# Main_Power.net
KiCad netlist of a schematic drawn in Altium Designer
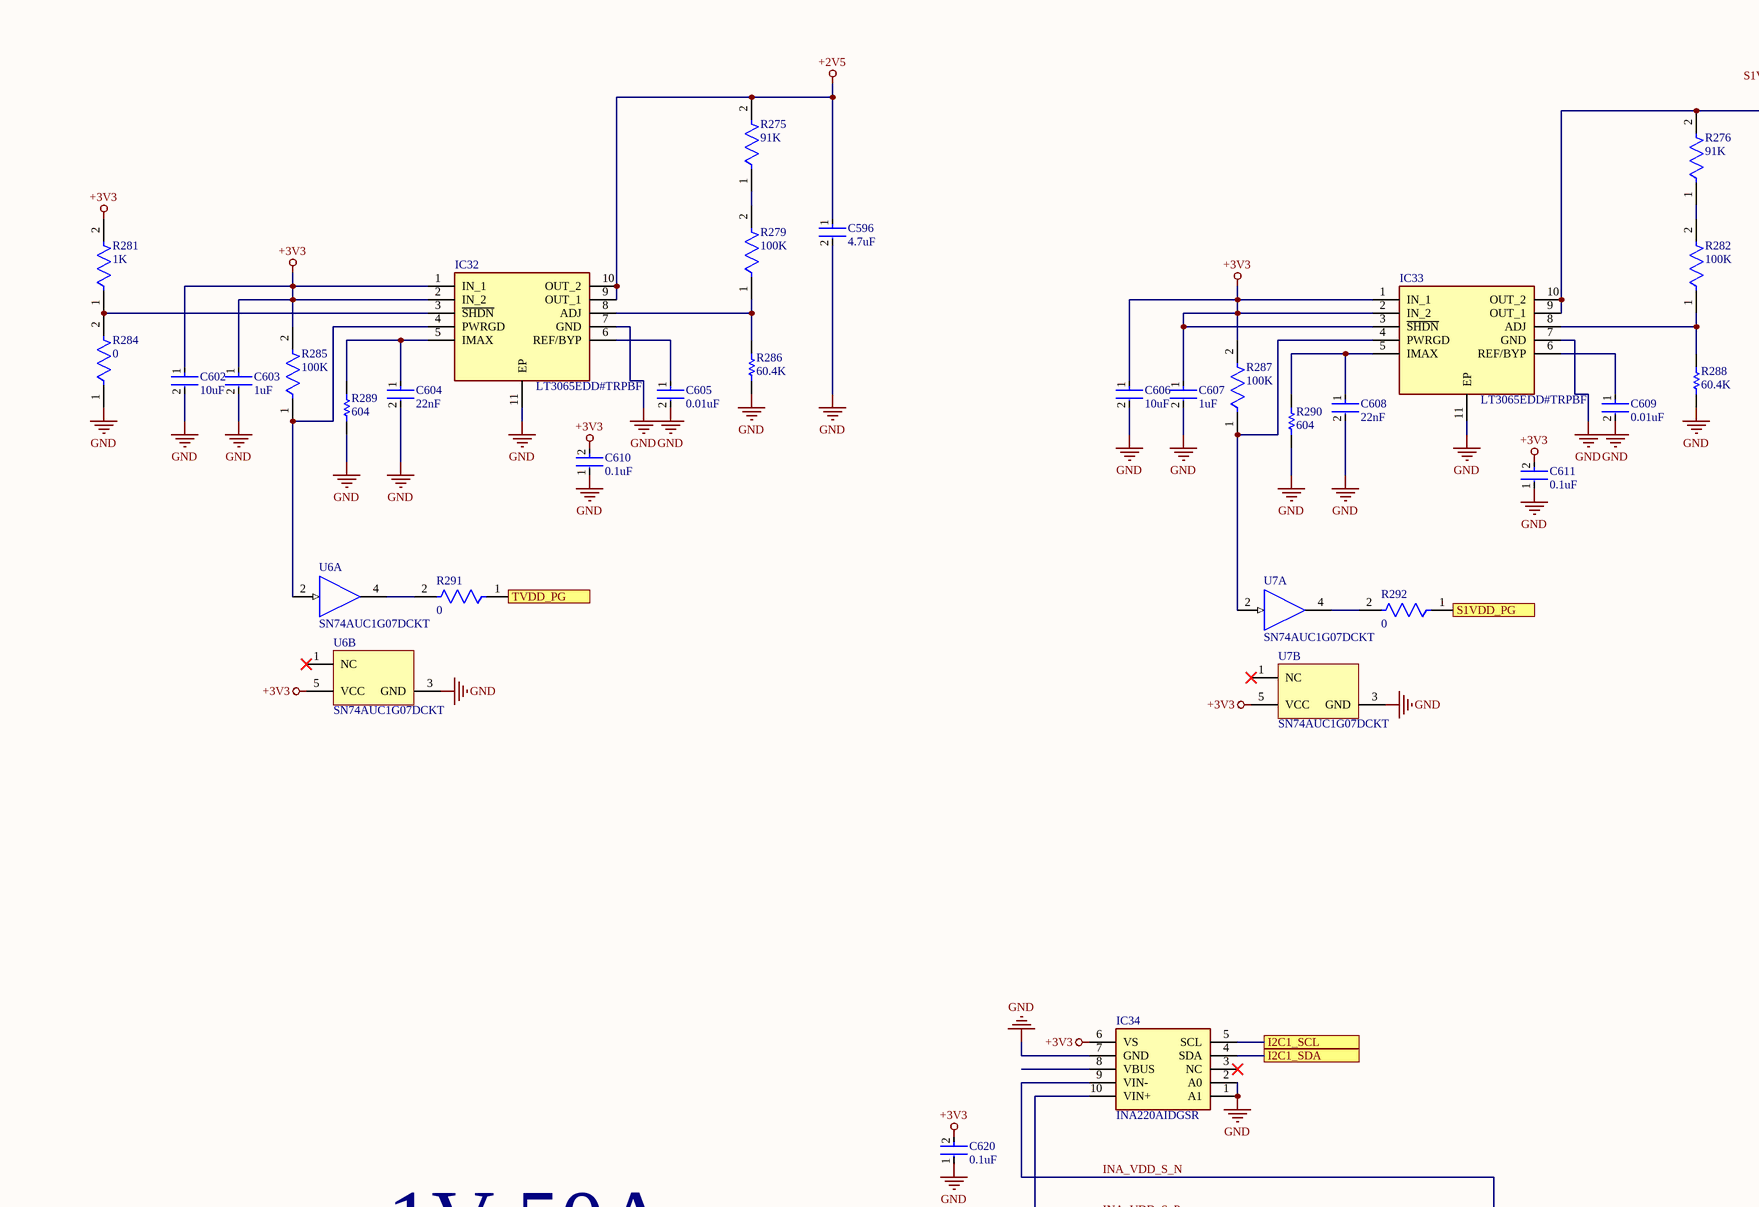
[diagram p0: Main_Power.SchDoc, top left]
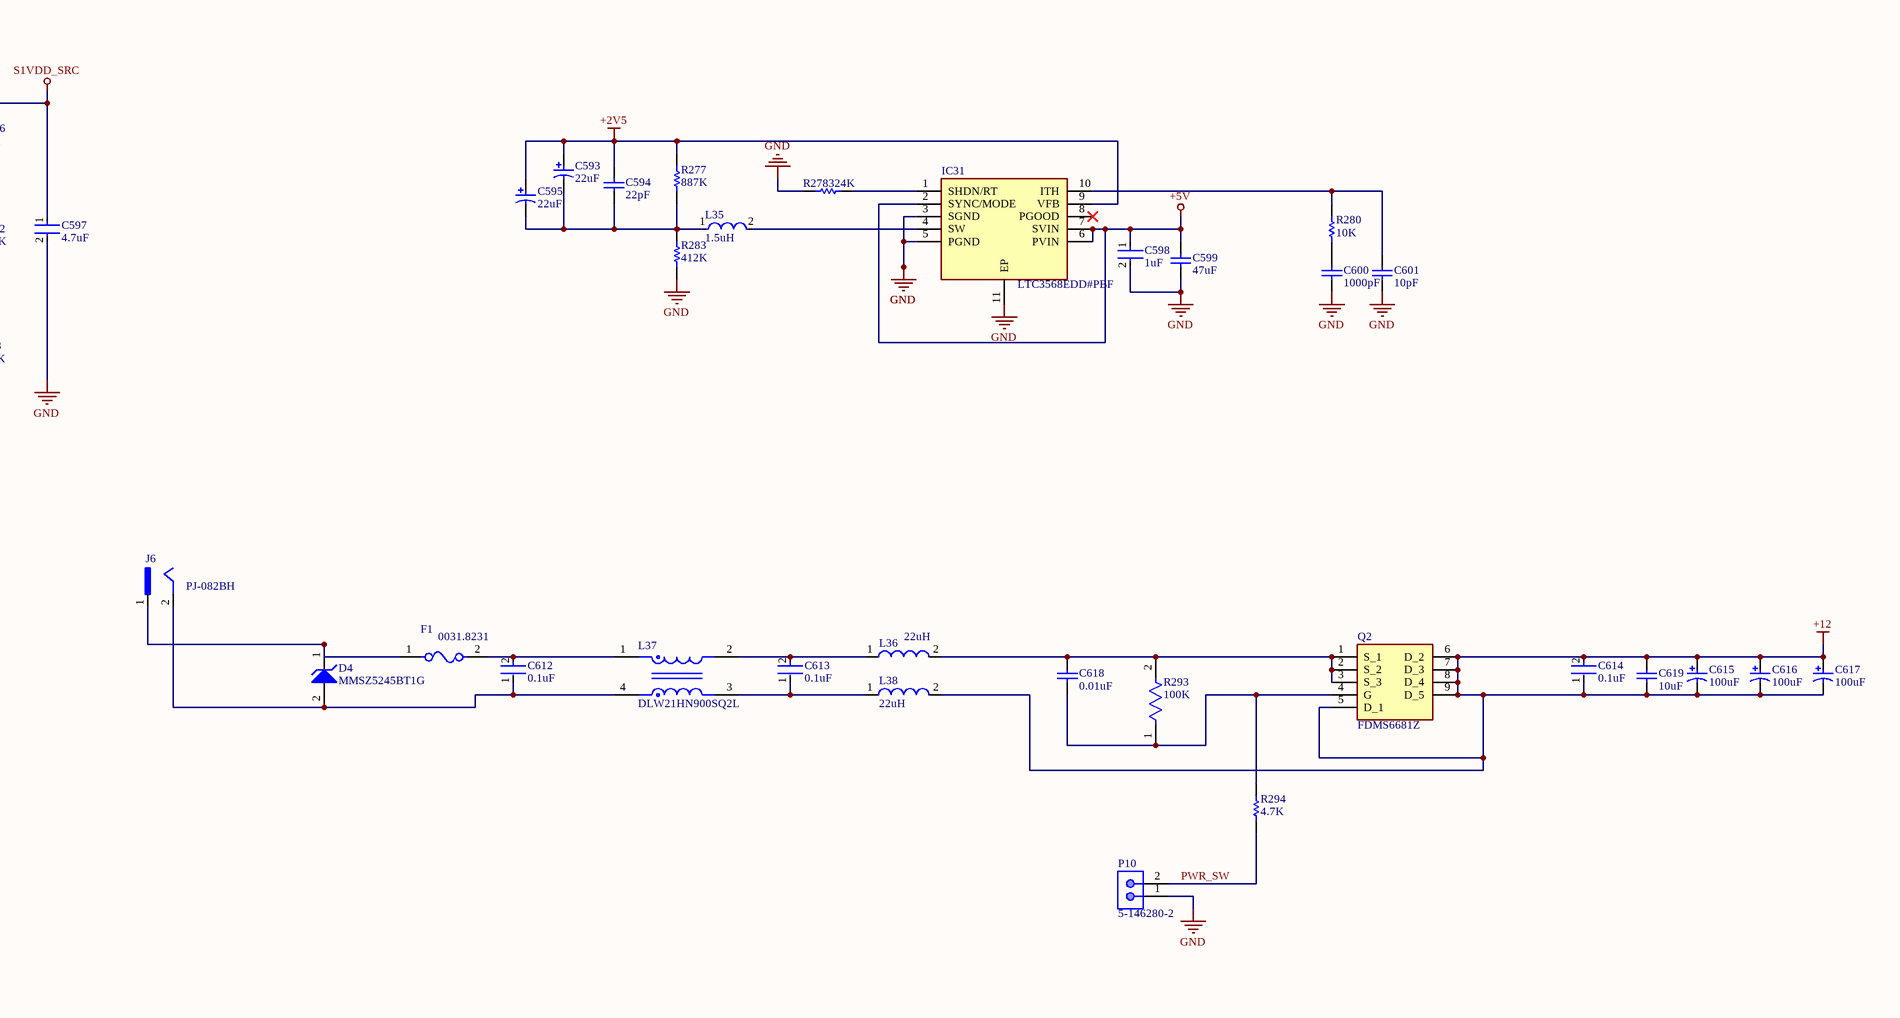
[diagram p1: Main_Power.SchDoc, top right]
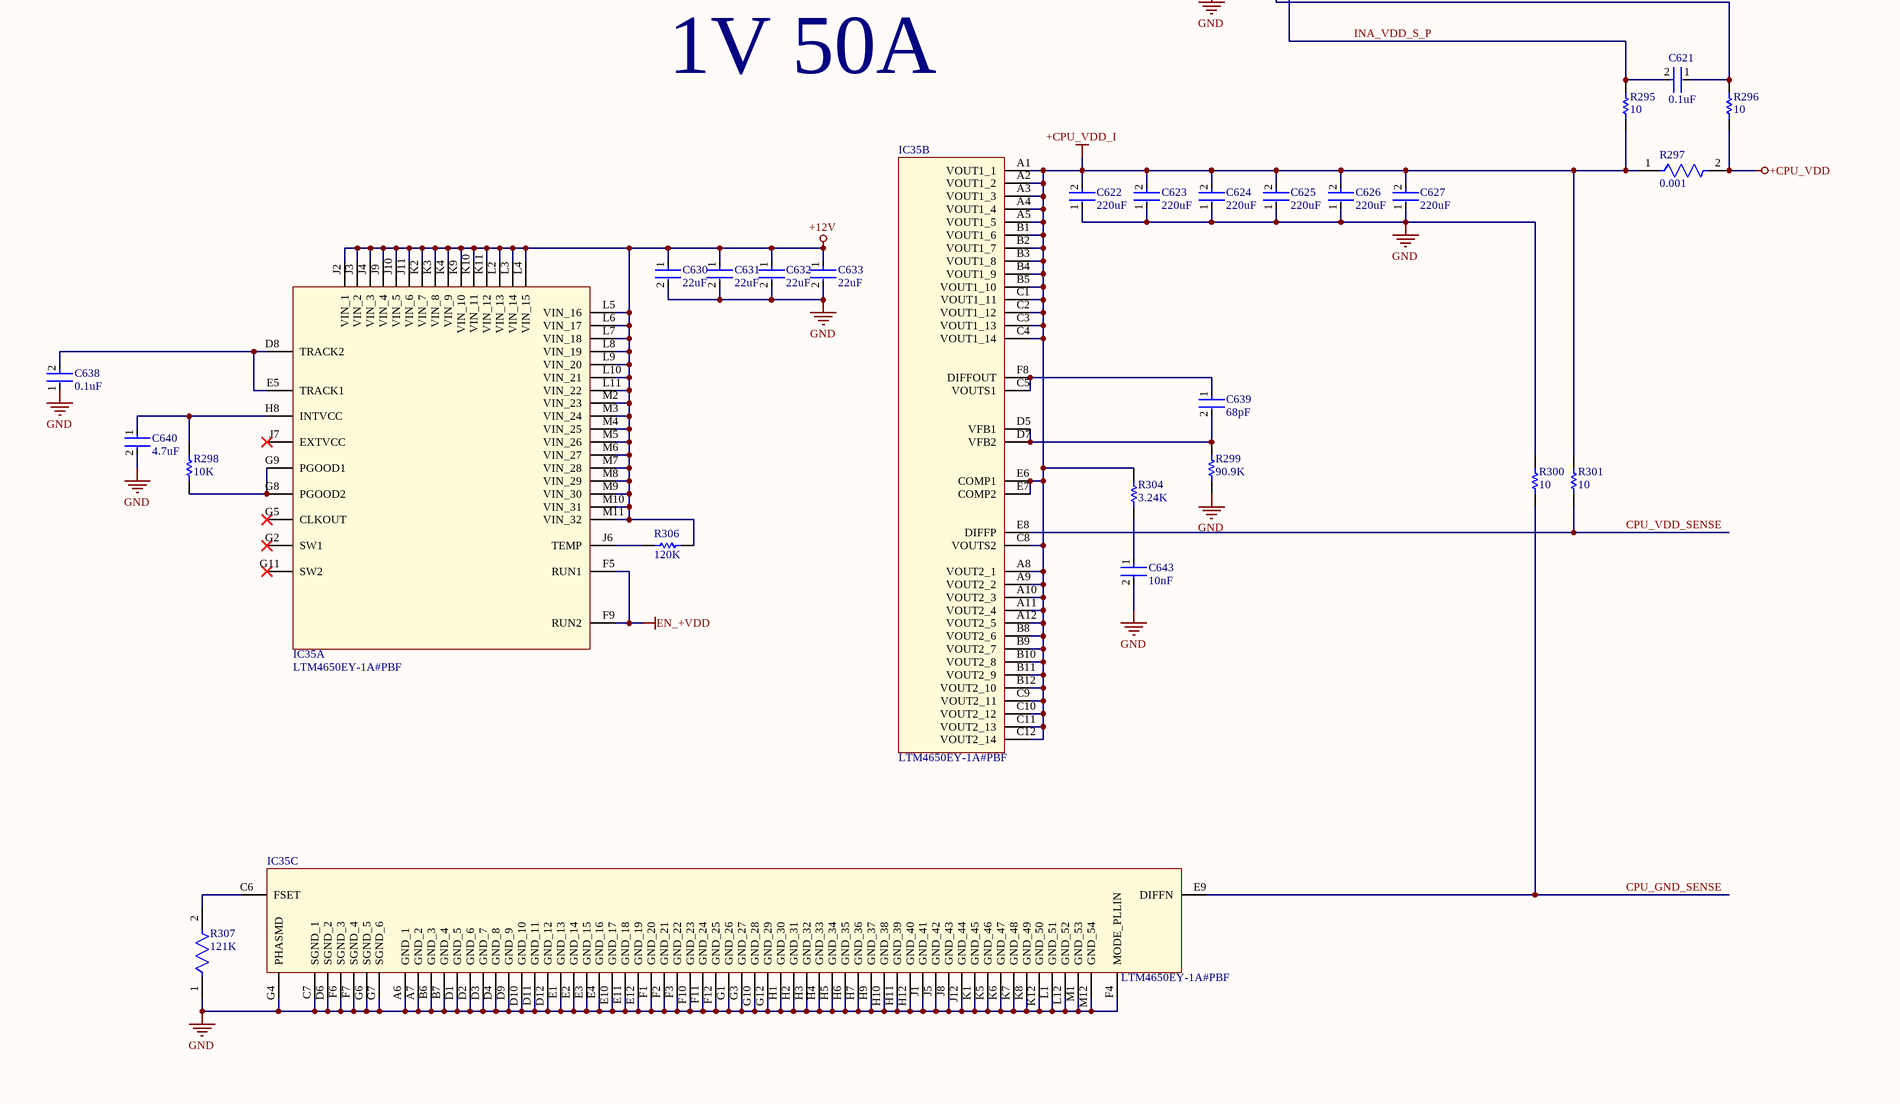
[diagram p2: Main_Power.SchDoc, bottom left]
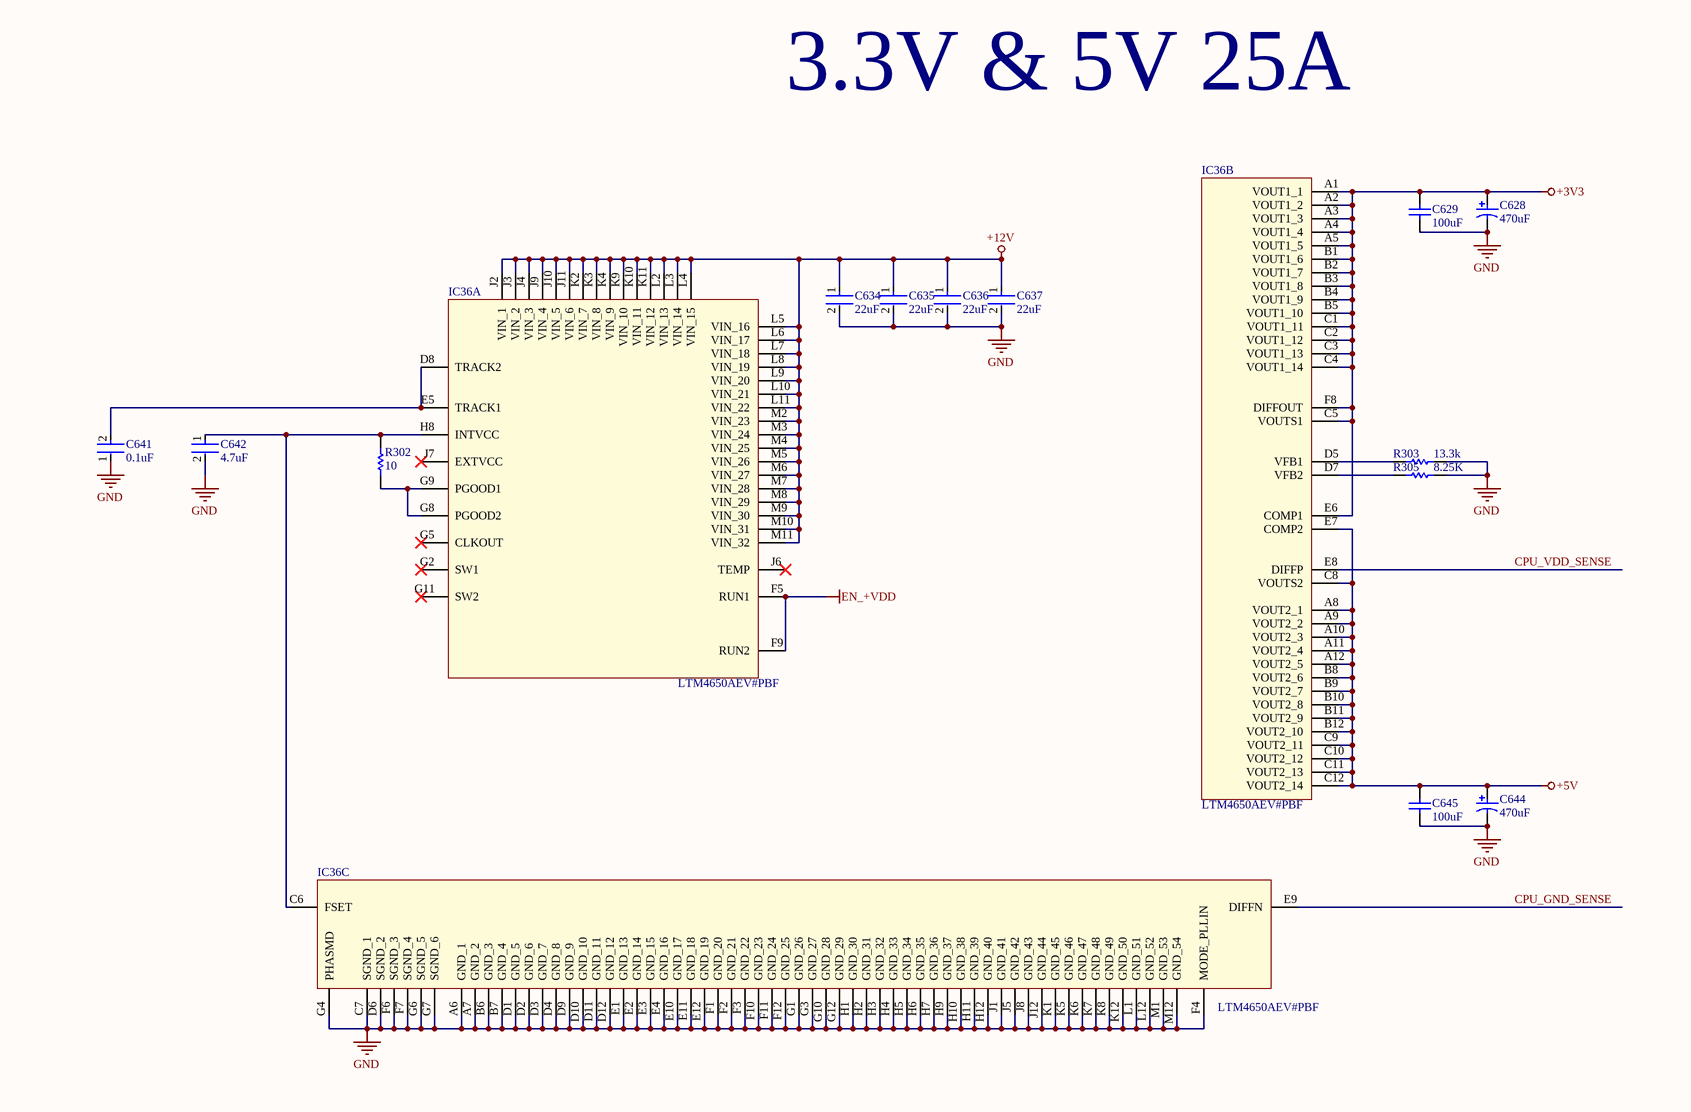
[diagram p3: Main_Power.SchDoc, bottom right]

(export (version "E")
  (design (tool "Eeschema 10.0.6"))
  (components
    (comp (ref "C593")
      (value "22uF")
      (footprint "AVX-TAJ-B-2_M")
      (description "Standard Tantalum, 22 uF, +/- 10%, 16 V, -55 to 125 degC, 2-Pin SMD (1210), RoHS, Tape and Reel")
      (fields (field (name "TOLERANCE") "10%") (field (name "MANUFACTURER") "AVX"))
      (libsource (lib "Altium Content Vault") (part "CAP-P-2"))
    )
    (comp (ref "C594")
      (value "22pF")
      (footprint "CAPC1005X55X25ML05T10")
      (fields (field (name "PART NUMBER") "GRM1555C1H220JZ01D") (field (name "MANUFACTURER") "Murata"))
      (libsource (lib "Altium Content Vault") (part "CAP"))
    )
    (comp (ref "C595")
      (value "22uF")
      (footprint "AVX-TAJ-B-2_M")
      (description "Standard Tantalum, 22 uF, +/- 10%, 16 V, -55 to 125 degC, 2-Pin SMD (1210), RoHS, Tape and Reel")
      (fields (field (name "TOLERANCE") "10%") (field (name "MANUFACTURER") "AVX"))
      (libsource (lib "Altium Content Vault") (part "CAP-P-2"))
    )
    (comp (ref "C596")
      (value "4.7uF")
      (footprint "FP-GRM155-0_1-IPC_B")
      (description "Chip Multilayer Ceramic Capacitors for General Purpose, 0402, 4.7uF, X5R, 15%, 20%, 6.3V")
      (fields (field (name "VOLTAGE") "6.3V") (field (name "TOLERANCE") "20%"))
      (libsource (lib "Altium Content Vault") (part "11868f565c42a9108669ba33697ecf6"))
    )
    (comp (ref "C597")
      (value "4.7uF")
      (footprint "FP-GRM155-0_1-IPC_B")
      (description "Chip Multilayer Ceramic Capacitors for General Purpose, 0402, 4.7uF, X5R, 15%, 20%, 6.3V")
      (fields (field (name "VOLTAGE") "6.3V") (field (name "TOLERANCE") "20%"))
      (libsource (lib "Altium Content Vault") (part "11868f565c42a9108669ba33697ecf6"))
    )
    (comp (ref "C598")
      (value "1uF")
      (footprint "FP-GRM15-0_1-MFG")
      (description "CAP CER 1UF 10V X5R 0402")
      (fields
        (field (name "OCTOPART") "https://octopart.com/grm155r61a105ke15d-murata-197442")
        (field (name "MANUFACTURER PART NUMBER") "GRM155R61A105KE15D")
      )
      (libsource (lib "Altium Content Vault") (part "02cd4be3c70576c341d710602a673aa"))
    )
    (comp (ref "C599")
      (value "47uF")
      (footprint "CAPC1206(3216)190_N")
      (description "CAP 47uF 10V ±20% 1206 (3216 Metric) Thickness 1.9mm SMD")
      (fields (field (name "TOLERANCE") "Â±20%"))
      (libsource (lib "Altium Content Vault") (part "CAP"))
    )
    (comp (ref "C600")
      (value "1000pF")
      (footprint "CAPC1005X55X25ML5T10")
      (description "Chip Capacitor, 1 nF, +/- 10%, 50 V, -55 to 125 degC, 0402 (1005 Metric), RoHS, Tape and Reel")
      (fields (field (name "TOLERANCE") "10%"))
      (libsource (lib "Altium Content Vault") (part "CAP-NP-2"))
    )
    (comp (ref "C601")
      (value "10pF")
      (footprint "CAPC1005X55X25ML05T10")
      (fields (field (name "PART NUMBER") "GRM1555C1H100JZ01D") (field (name "MANUFACTURER") "Murata"))
      (libsource (lib "Altium Content Vault") (part "CAP"))
    )
    (comp (ref "C602")
      (value "10uF")
      (footprint "FP-C0805C-DG-MFG")
      (description "CAP CER 10UF 10V X5R 0805")
      (fields (field (name "TOLERANCE") "10%") (field (name "MANUFACTURER PART NUMBER") "C0805C106K8PACTU"))
      (libsource (lib "Altium Content Vault") (part "11868f565c42a9108669ba33697ecf6"))
    )
    (comp (ref "C603")
      (value "1uF")
      (footprint "FP-GRM15-0_1-MFG")
      (description "CAP CER 1UF 10V X5R 0402")
      (fields
        (field (name "OCTOPART") "https://octopart.com/grm155r61a105ke15d-murata-197442")
        (field (name "MANUFACTURER PART NUMBER") "GRM155R61A105KE15D")
      )
      (libsource (lib "Altium Content Vault") (part "02cd4be3c70576c341d710602a673aa"))
    )
    (comp (ref "C604")
      (value "22nF")
      (footprint "FP-CL288-IPC_C")
      (description "Cap Ceramic 22nF 16V X7R ±10% SMD 0402 +125°C Paper T/R")
      (fields (field (name "TOLERANCE") "10%") (field (name "VOLTAGE") "16V"))
      (libsource (lib "Altium Content Vault") (part "b4654b650e69147ec39a6b967a45e02"))
    )
    (comp (ref "C605")
      (value "0.01uF")
      (footprint "FP-C0402-BB-MFG")
      (description "CAP CER 10000PF 16V X7R 0402")
      (fields (field (name "TOLERANCE") "0.1") (field (name "MANUFACTURER PART NUMBER") "C0402C103K4RACTU"))
      (libsource (lib "Altium Content Vault") (part "b4654b650e69147ec39a6b967a45e02"))
    )
    (comp (ref "C606")
      (value "10uF")
      (footprint "FP-C0805C-DG-MFG")
      (description "CAP CER 10UF 10V X5R 0805")
      (fields (field (name "TOLERANCE") "10%") (field (name "MANUFACTURER PART NUMBER") "C0805C106K8PACTU"))
      (libsource (lib "Altium Content Vault") (part "11868f565c42a9108669ba33697ecf6"))
    )
    (comp (ref "C607")
      (value "1uF")
      (footprint "FP-GRM15-0_1-MFG")
      (description "CAP CER 1UF 10V X5R 0402")
      (fields
        (field (name "OCTOPART") "https://octopart.com/grm155r61a105ke15d-murata-197442")
        (field (name "MANUFACTURER PART NUMBER") "GRM155R61A105KE15D")
      )
      (libsource (lib "Altium Content Vault") (part "02cd4be3c70576c341d710602a673aa"))
    )
    (comp (ref "C608")
      (value "22nF")
      (footprint "FP-CL288-IPC_C")
      (description "Cap Ceramic 22nF 16V X7R ±10% SMD 0402 +125°C Paper T/R")
      (fields (field (name "TOLERANCE") "10%") (field (name "VOLTAGE") "16V"))
      (libsource (lib "Altium Content Vault") (part "b4654b650e69147ec39a6b967a45e02"))
    )
    (comp (ref "C609")
      (value "0.01uF")
      (footprint "FP-C0402-BB-MFG")
      (description "CAP CER 10000PF 16V X7R 0402")
      (fields (field (name "TOLERANCE") "0.1") (field (name "MANUFACTURER PART NUMBER") "C0402C103K4RACTU"))
      (libsource (lib "Altium Content Vault") (part "b4654b650e69147ec39a6b967a45e02"))
    )
    (comp (ref "C610")
      (value "0.1uF")
      (footprint "FP-GRM15-MFG")
      (description "CAP CER 0.1UF 16V X7R 0402")
      (fields (field (name "MANUFACTURER PART NUMBER") "GRM155R71C104KA88D") (field (name "TOLERANCE") "10%"))
      (libsource (lib "Altium Content Vault") (part "236180d848d6139a670b325ea6854c9"))
    )
    (comp (ref "C611")
      (value "0.1uF")
      (footprint "FP-GRM15-MFG")
      (description "CAP CER 0.1UF 16V X7R 0402")
      (fields (field (name "MANUFACTURER PART NUMBER") "GRM155R71C104KA88D") (field (name "TOLERANCE") "10%"))
      (libsource (lib "Altium Content Vault") (part "236180d848d6139a670b325ea6854c9"))
    )
    (comp (ref "C612")
      (value "0.1uF")
      (footprint "FP-GRM15-MFG")
      (description "CAP CER 0.1UF 16V X7R 0402")
      (fields (field (name "MANUFACTURER PART NUMBER") "GRM155R71C104KA88D") (field (name "TOLERANCE") "10%"))
      (libsource (lib "Altium Content Vault") (part "236180d848d6139a670b325ea6854c9"))
    )
    (comp (ref "C613")
      (value "0.1uF")
      (footprint "FP-GRM15-MFG")
      (description "CAP CER 0.1UF 16V X7R 0402")
      (fields (field (name "MANUFACTURER PART NUMBER") "GRM155R71C104KA88D") (field (name "TOLERANCE") "10%"))
      (libsource (lib "Altium Content Vault") (part "236180d848d6139a670b325ea6854c9"))
    )
    (comp (ref "C614")
      (value "0.1uF")
      (footprint "FP-GRM15-MFG")
      (description "CAP CER 0.1UF 16V X7R 0402")
      (fields (field (name "MANUFACTURER PART NUMBER") "GRM155R71C104KA88D") (field (name "TOLERANCE") "10%"))
      (libsource (lib "Altium Content Vault") (part "236180d848d6139a670b325ea6854c9"))
    )
    (comp (ref "C615")
      (value "100uF")
      (footprint "PNSC-FK-V-D8_V")
      (fields (field (name "MANUFACTURER") "Panasonic"))
      (libsource (lib "Altium Content Vault") (part "CAP-P-2"))
    )
    (comp (ref "C616")
      (value "100uF")
      (footprint "PNSC-FK-V-D8_V")
      (fields (field (name "MANUFACTURER") "Panasonic"))
      (libsource (lib "Altium Content Vault") (part "CAP-P-2"))
    )
    (comp (ref "C617")
      (value "100uF")
      (footprint "PNSC-FK-V-D8_V")
      (fields (field (name "MANUFACTURER") "Panasonic"))
      (libsource (lib "Altium Content Vault") (part "CAP-P-2"))
    )
    (comp (ref "C618")
      (value "0.01uF")
      (footprint "CAPC1005X56X25LL10T15")
      (fields
        (field (name "MANUFACTURER") "AVX Interconnect / Elco")
        (field (name "PART NUMBER") "0402YC103JAT2A")
      )
      (libsource (lib "Altium Content Vault") (part "CAP"))
    )
    (comp (ref "C619")
      (value "10uF")
      (footprint "CAPC1210(3225)190_N")
      (description "CAP 10uF 16V -20% to +80% 1210 (3225 Metric) Thickness 1.9mm SMD")
      (fields (field (name "TOLERANCE") "-20% to +80%"))
      (libsource (lib "Altium Content Vault") (part "CAP"))
    )
    (comp (ref "C620")
      (value "0.1uF")
      (footprint "FP-GRM15-MFG")
      (description "CAP CER 0.1UF 16V X7R 0402")
      (fields (field (name "MANUFACTURER PART NUMBER") "GRM155R71C104KA88D") (field (name "TOLERANCE") "10%"))
      (libsource (lib "Altium Content Vault") (part "236180d848d6139a670b325ea6854c9"))
    )
    (comp (ref "C621")
      (value "0.1uF")
      (footprint "FP-GRM15-MFG")
      (description "CAP CER 0.1UF 16V X7R 0402")
      (fields (field (name "MANUFACTURER PART NUMBER") "GRM155R71C104KA88D") (field (name "TOLERANCE") "10%"))
      (libsource (lib "Altium Content Vault") (part "236180d848d6139a670b325ea6854c9"))
    )
    (comp (ref "C622")
      (value "220uF")
      (footprint "FP-GRM31C-0_3-e0_3_0_9-IPC_C")
      (description "Chip Multilayer Ceramic Capacitors for General Purpose, 1206, 220uF, X5R, 15%, 20%, 6.3V")
      (fields (field (name "TOLERANCE") "20%"))
      (libsource (lib "Altium Content Vault") (part "f23184f103b6ebe33a8c269c53dcba6"))
    )
    (comp (ref "C623")
      (value "220uF")
      (footprint "FP-GRM31C-0_3-e0_3_0_9-IPC_C")
      (description "Chip Multilayer Ceramic Capacitors for General Purpose, 1206, 220uF, X5R, 15%, 20%, 6.3V")
      (fields (field (name "TOLERANCE") "20%"))
      (libsource (lib "Altium Content Vault") (part "f23184f103b6ebe33a8c269c53dcba6"))
    )
    (comp (ref "C624")
      (value "220uF")
      (footprint "FP-GRM31C-0_3-e0_3_0_9-IPC_C")
      (description "Chip Multilayer Ceramic Capacitors for General Purpose, 1206, 220uF, X5R, 15%, 20%, 6.3V")
      (fields (field (name "TOLERANCE") "20%"))
      (libsource (lib "Altium Content Vault") (part "f23184f103b6ebe33a8c269c53dcba6"))
    )
    (comp (ref "C625")
      (value "220uF")
      (footprint "FP-GRM31C-0_3-e0_3_0_9-IPC_C")
      (description "Chip Multilayer Ceramic Capacitors for General Purpose, 1206, 220uF, X5R, 15%, 20%, 6.3V")
      (fields (field (name "TOLERANCE") "20%"))
      (libsource (lib "Altium Content Vault") (part "f23184f103b6ebe33a8c269c53dcba6"))
    )
    (comp (ref "C626")
      (value "220uF")
      (footprint "FP-GRM31C-0_3-e0_3_0_9-IPC_C")
      (description "Chip Multilayer Ceramic Capacitors for General Purpose, 1206, 220uF, X5R, 15%, 20%, 6.3V")
      (fields (field (name "TOLERANCE") "20%"))
      (libsource (lib "Altium Content Vault") (part "f23184f103b6ebe33a8c269c53dcba6"))
    )
    (comp (ref "C627")
      (value "220uF")
      (footprint "FP-GRM31C-0_3-e0_3_0_9-IPC_C")
      (description "Chip Multilayer Ceramic Capacitors for General Purpose, 1206, 220uF, X5R, 15%, 20%, 6.3V")
      (fields (field (name "TOLERANCE") "20%"))
      (libsource (lib "Altium Content Vault") (part "f23184f103b6ebe33a8c269c53dcba6"))
    )
    (comp (ref "C628")
      (value "470uF")
      (footprint "KEMT-T495-X_L")
      (description "Tantalum Capacitor, 470 uF, +/- 10%, 10 V, -55 to 125 degC, 2-Pin SMD, RoHS, Tape and Reel")
      (fields (field (name "MANUFACTURER") "Kemet") (field (name "TOLERANCE") "10%"))
      (libsource (lib "Altium Content Vault") (part "CAP-P-2"))
    )
    (comp (ref "C629")
      (value "100uF")
      (footprint "CAPC3225X280X50LL20T25")
      (description "Chip Capacitor, 100 uF, +/- 20%, 6.3 V, -55 to 85 degC, 1210 (3225 Metric), RoHS, Tape and Reel")
      (fields (field (name "TOLERANCE") "20%") (field (name "VOLTAGE") "6.3Vdc"))
      (libsource (lib "") (part "CAP-NP-2_1"))
    )
    (comp (ref "C630")
      (value "22uF")
      (footprint "FP-GRM32-MFG")
      (description "CAP CER 22UF 25V X5R 1210")
      (fields
        (field (name "TOLERANCE") "10%")
        (field (name "MANUFACTURER") "Murata Electronics North America")
      )
      (libsource (lib "Altium Content Vault") (part "11868f565c42a9108669ba33697ecf6"))
    )
    (comp (ref "C631")
      (value "22uF")
      (footprint "FP-GRM32-MFG")
      (description "CAP CER 22UF 25V X5R 1210")
      (fields
        (field (name "TOLERANCE") "10%")
        (field (name "MANUFACTURER") "Murata Electronics North America")
      )
      (libsource (lib "Altium Content Vault") (part "11868f565c42a9108669ba33697ecf6"))
    )
    (comp (ref "C632")
      (value "22uF")
      (footprint "FP-GRM32-MFG")
      (description "CAP CER 22UF 25V X5R 1210")
      (fields
        (field (name "TOLERANCE") "10%")
        (field (name "MANUFACTURER") "Murata Electronics North America")
      )
      (libsource (lib "Altium Content Vault") (part "11868f565c42a9108669ba33697ecf6"))
    )
    (comp (ref "C633")
      (value "22uF")
      (footprint "FP-GRM32-MFG")
      (description "CAP CER 22UF 25V X5R 1210")
      (fields
        (field (name "TOLERANCE") "10%")
        (field (name "MANUFACTURER") "Murata Electronics North America")
      )
      (libsource (lib "Altium Content Vault") (part "11868f565c42a9108669ba33697ecf6"))
    )
    (comp (ref "C634")
      (value "22uF")
      (footprint "FP-GRM32-MFG")
      (description "CAP CER 22UF 25V X5R 1210")
      (fields
        (field (name "TOLERANCE") "10%")
        (field (name "MANUFACTURER") "Murata Electronics North America")
      )
      (libsource (lib "Altium Content Vault") (part "11868f565c42a9108669ba33697ecf6"))
    )
    (comp (ref "C635")
      (value "22uF")
      (footprint "FP-GRM32-MFG")
      (description "CAP CER 22UF 25V X5R 1210")
      (fields
        (field (name "TOLERANCE") "10%")
        (field (name "MANUFACTURER") "Murata Electronics North America")
      )
      (libsource (lib "Altium Content Vault") (part "11868f565c42a9108669ba33697ecf6"))
    )
    (comp (ref "C636")
      (value "22uF")
      (footprint "FP-GRM32-MFG")
      (description "CAP CER 22UF 25V X5R 1210")
      (fields
        (field (name "TOLERANCE") "10%")
        (field (name "MANUFACTURER") "Murata Electronics North America")
      )
      (libsource (lib "Altium Content Vault") (part "11868f565c42a9108669ba33697ecf6"))
    )
    (comp (ref "C637")
      (value "22uF")
      (footprint "FP-GRM32-MFG")
      (description "CAP CER 22UF 25V X5R 1210")
      (fields
        (field (name "TOLERANCE") "10%")
        (field (name "MANUFACTURER") "Murata Electronics North America")
      )
      (libsource (lib "Altium Content Vault") (part "11868f565c42a9108669ba33697ecf6"))
    )
    (comp (ref "C638")
      (value "0.1uF")
      (footprint "FP-GRM15-MFG")
      (description "CAP CER 0.1UF 16V X7R 0402")
      (fields (field (name "MANUFACTURER PART NUMBER") "GRM155R71C104KA88D") (field (name "TOLERANCE") "10%"))
      (libsource (lib "Altium Content Vault") (part "236180d848d6139a670b325ea6854c9"))
    )
    (comp (ref "C639")
      (value "68pF")
      (footprint "FP-C0805C-DN-MFG")
      (description "CAP CER 68PF 50V C0G/NP0 0805")
      (fields
        (field (name "MANUFACTURER PART NUMBER") "C0805C680J5GACTU")
        (field (name "OCTOPART") "https://octopart.com/c0805c680j5gactu-kemet-130145")
      )
      (libsource (lib "Altium Content Vault") (part "b4654b650e69147ec39a6b967a45e02"))
    )
    (comp (ref "C640")
      (value "4.7uF")
      (footprint "FP-GRM155-0_1-IPC_B")
      (description "Chip Multilayer Ceramic Capacitors for General Purpose, 0402, 4.7uF, X5R, 15%, 20%, 6.3V")
      (fields (field (name "VOLTAGE") "6.3V") (field (name "TOLERANCE") "20%"))
      (libsource (lib "Altium Content Vault") (part "11868f565c42a9108669ba33697ecf6"))
    )
    (comp (ref "C641")
      (value "0.1uF")
      (footprint "FP-GRM15-MFG")
      (description "CAP CER 0.1UF 16V X7R 0402")
      (fields (field (name "MANUFACTURER PART NUMBER") "GRM155R71C104KA88D") (field (name "TOLERANCE") "10%"))
      (libsource (lib "Altium Content Vault") (part "236180d848d6139a670b325ea6854c9"))
    )
    (comp (ref "C642")
      (value "4.7uF")
      (footprint "FP-GRM155-0_1-IPC_B")
      (description "Chip Multilayer Ceramic Capacitors for General Purpose, 0402, 4.7uF, X5R, 15%, 20%, 6.3V")
      (fields (field (name "VOLTAGE") "6.3V") (field (name "TOLERANCE") "20%"))
      (libsource (lib "Altium Content Vault") (part "11868f565c42a9108669ba33697ecf6"))
    )
    (comp (ref "C643")
      (value "10nF")
      (footprint "FP-CC0603-DA-MFG")
      (description "CAP CER 10000PF 50V X7R 0603")
      (fields (field (name "TOLERANCE") "0.1") (field (name "MANUFACTURER PART NUMBER") "CC0603KRX7R9BB103"))
      (libsource (lib "Altium Content Vault") (part "11868f565c42a9108669ba33697ecf6"))
    )
    (comp (ref "C644")
      (value "470uF")
      (footprint "KEMT-T495-X_L")
      (description "Tantalum Capacitor, 470 uF, +/- 10%, 10 V, -55 to 125 degC, 2-Pin SMD, RoHS, Tape and Reel")
      (fields (field (name "MANUFACTURER") "Kemet") (field (name "TOLERANCE") "10%"))
      (libsource (lib "Altium Content Vault") (part "CAP-P-2"))
    )
    (comp (ref "C645")
      (value "100uF")
      (footprint "CAPC3225X280X50LL20T25")
      (description "Chip Capacitor, 100 uF, +/- 20%, 6.3 V, -55 to 85 degC, 1210 (3225 Metric), RoHS, Tape and Reel")
      (fields (field (name "TOLERANCE") "20%") (field (name "VOLTAGE") "6.3Vdc"))
      (libsource (lib "") (part "CAP-NP-2_1"))
    )
    (comp (ref "D4")
      (value "MMSZ5245BT1G")
      (footprint "ONSC-SOD-123-2-425-04_V")
      (description "Zener Voltage Regulator, 500 mW, 2-Pin SOD-123, Pb-Free, Tape and Reel")
      (fields (field (name "MANUFACTURER") "On Semiconductor"))
      (libsource (lib "Altium Content Vault") (part "ONSC-K1A2-2"))
    )
    (comp (ref "F1")
      (value "0031.8231")
      (footprint "FP-0031_8231-MFG")
      (description "FUSE BLOK CARTRIDGE 600V 16A PCB")
      (fields
        (field (name "OCTOPART") "https://octopart.com/0031.8231-schurter-8659")
        (field (name "MANUFACTURER") "Schurter")
      )
      (libsource (lib "Altium Content Vault") (part "5bcf9b9f640e542cf0359d10258e979"))
    )
    (comp (ref "IC31")
      (value "LTC3568EDD#PBF")
      (footprint "SamacSys:SON50P300X300X80-11N-D")
      (description "Integrated Circuit")
      (libsource (lib "*") (part "LTC3568EDD#PBF"))
    )
    (comp (ref "IC32")
      (value "LT3065EDD#TRPBF")
      (footprint "SamacSys:SON50P300X300X80-11N-D")
      (description "Integrated Circuit")
      (fields (field (name "MOUSER PART NUMBER") "584-LT3065EDD#TRPBF"))
      (libsource (lib "*") (part "LT3065EDD#TRPBF"))
    )
    (comp (ref "IC33")
      (value "LT3065EDD#TRPBF")
      (footprint "SamacSys:SON50P300X300X80-11N-D")
      (description "Integrated Circuit")
      (fields (field (name "MOUSER PART NUMBER") "584-LT3065EDD#TRPBF"))
      (libsource (lib "*") (part "LT3065EDD#TRPBF"))
    )
    (comp (ref "IC34")
      (value "INA220AIDGSR")
      (footprint "SamacSys:SOP50P490X110-10N")
      (description "Integrated Circuit")
      (fields (field (name "MOUSER PART NUMBER") "595-INA220AIDGSR"))
      (libsource (lib "*") (part "INA220AIDGSR"))
    )
    (comp (ref "IC35")
      (value "LTM4650EY-1A#PBF")
      (footprint "SamacSys:BGA144C127P12X12_1600X1600X521")
      (description "Integrated Circuit")
      (fields (field (name "MOUSER PART NUMBER") "584-LTM4650EY-1A#PBF"))
      (libsource (lib "SamacSys") (part "LTM4650EY-1A#PBF"))
    )
    (comp (ref "IC36")
      (value "LTM4650AEV#PBF")
      (footprint "SamacSys:BGA144C127P12X12_1600X1600X521")
      (description "Integrated Circuit")
      (libsource (lib "SamacSys") (part "LTM4650AEV#PBF"))
    )
    (comp (ref "J6")
      (value "PJ-082BH")
      (footprint "PJ-082BH:CUI_PJ-082BH")
      (description "2.5 mm Center Pin, 10 A, Right Angle, Through Hole, Shielded, Dc Power Jack Connector")
      (fields (field (name "MF") "{'manufacturer': u'CUI Devices'}"))
      (libsource (lib "*") (part "PJ-082BH"))
    )
    (comp (ref "L35")
      (value "1.5uH")
      (footprint "FP-IHLP-6767GZ-FP_3_825x1-MFG")
      (description "Commercial Inductors, Low DCR Series 1.5uH 48A 1.62mΩ 20%")
      (fields (field (name "TOLERANCE") "20%"))
      (libsource (lib "Altium Content Vault") (part "725321dda6339637d4d059423bc1c3c"))
    )
    (comp (ref "L36")
      (value "22uH")
      (footprint "WE-HCI-1365")
      (description "SMD Flat Wire High Current Inductor WE-HCI, L=22.0 µH")
      (libsource (lib "Altium Content Vault") (part "PAS-IND-INDUCTOR-2"))
    )
    (comp (ref "L37")
      (value "DLW21HN900SQ2L")
      (footprint "FP-DLW21HN-MFG")
      (description "CMC 330MA 2LN 90 OHM SMD")
      (fields (field (name "TOLERANCE") "25%"))
      (libsource (lib "Altium Content Vault") (part "0a69a9865a8fa8fb197e9315ef85d0a"))
    )
    (comp (ref "L38")
      (value "22uH")
      (footprint "WE-HCI-1365")
      (description "SMD Flat Wire High Current Inductor WE-HCI, L=22.0 µH")
      (libsource (lib "Altium Content Vault") (part "PAS-IND-INDUCTOR-2"))
    )
    (comp (ref "P10")
      (value "5-146280-2")
      (footprint "TECO-5-146280-2_V")
      (fields (field (name "MANUFACTURER") "TE Connectivity"))
      (libsource (lib "Altium Content Vault") (part "CN-1P-M-R2"))
    )
    (comp (ref "Q2")
      (value "FDMS6681Z")
      (footprint "SamacSys:FDMS6681Z")
      (description "MOSFET (P-Channel)")
      (fields (field (name "MOUSER PART NUMBER") "512-FDMS6681Z"))
      (libsource (lib "SamacSys") (part "FDMS6681Z"))
    )
    (comp (ref "R275")
      (value "91K")
      (footprint "FP-CRCW0402-e3-IPC_B")
      (description "RES Thick Film, 91kΩ, 1%, 0.063W, 100ppm/°C, 0402")
      (fields (field (name "TOLERANCE") "1%"))
      (libsource (lib "Altium Content Vault") (part "1029c3af85768c4190bb7ad29bc67b5"))
    )
    (comp (ref "R276")
      (value "91K")
      (footprint "FP-CRCW0402-e3-IPC_B")
      (description "RES Thick Film, 91kΩ, 1%, 0.063W, 100ppm/°C, 0402")
      (fields (field (name "TOLERANCE") "1%"))
      (libsource (lib "Altium Content Vault") (part "1029c3af85768c4190bb7ad29bc67b5"))
    )
    (comp (ref "R277")
      (value "887K")
      (footprint "RESC1005X40X25ML05T05")
      (fields (field (name "PART NUMBER") "CRCW0402887KFKED") (field (name "MANUFACTURER") "Vishay Dale"))
      (libsource (lib "Altium Content Vault") (part "RES"))
    )
    (comp (ref "R278")
      (value "324K")
      (footprint "RESC1005X40X25LL05T05")
      (description "Chip Resistor, 324 KOhm, +/- 1%, 0.1 W, -55 to 155 degC, 0402 (1005 Metric), RoHS, Tape and Reel")
      (fields (field (name "TOLERANCE") "1%") (field (name "PARTNUMBER") "ERJ-2RKF3243X"))
      (libsource (lib "Altium Content Vault") (part "RES-2"))
    )
    (comp (ref "R279")
      (value "100K")
      (footprint "FP-CRCW0402-e3-IPC_C")
      (description "RES Thick Film, 100kΩ, 1%, 0.063W, 100ppm/°C, 0402")
      (fields (field (name "TOLERANCE") "1%"))
      (libsource (lib "Altium Content Vault") (part "1029c3af85768c4190bb7ad29bc67b5"))
    )
    (comp (ref "R280")
      (value "10K")
      (footprint "RESC1005X40X25LL05T05")
      (description "Chip Resistor, 10 KOhm, +/- 1%, 0.1 W, -55 to 155 degC, 0402 (1005 Metric), RoHS, Tape and Reel")
      (fields (field (name "TOLERANCE") "1%") (field (name "MANUFACTURER") "Panasonic"))
      (libsource (lib "Altium Content Vault") (part "RES-2"))
    )
    (comp (ref "R281")
      (value "1K")
      (footprint "FP-CRCW0402-e3-MFG")
      (description "RES Thick Film, 1kΩ, 1%, 0.063W, 100ppm/°C, 0402")
      (fields (field (name "TOLERANCE") "1%"))
      (libsource (lib "Altium Content Vault") (part "1029c3af85768c4190bb7ad29bc67b5"))
    )
    (comp (ref "R282")
      (value "100K")
      (footprint "FP-CRCW0402-e3-IPC_C")
      (description "RES Thick Film, 100kΩ, 1%, 0.063W, 100ppm/°C, 0402")
      (fields (field (name "TOLERANCE") "1%"))
      (libsource (lib "Altium Content Vault") (part "1029c3af85768c4190bb7ad29bc67b5"))
    )
    (comp (ref "R283")
      (value "412K")
      (footprint "RESC1005X40X25LL05T05")
      (fields (field (name "MANUFACTURER") "Vishay Dale") (field (name "PART NUMBER") "CRCW0402412KFKED"))
      (libsource (lib "Altium Content Vault") (part "RES"))
    )
    (comp (ref "R284")
      (value "0")
      (footprint "FP-CRCW0402-e3-IPC_C")
      (description "RES Thick Film, 0Ω, 0.063W, 0402")
      (fields (field (name "TOLERANCE") "5%"))
      (libsource (lib "Altium Content Vault") (part "1029c3af85768c4190bb7ad29bc67b5"))
    )
    (comp (ref "R285")
      (value "100K")
      (footprint "FP-CRCW0402-e3-IPC_C")
      (description "RES Thick Film, 100kΩ, 1%, 0.063W, 100ppm/°C, 0402")
      (fields (field (name "TOLERANCE") "1%"))
      (libsource (lib "Altium Content Vault") (part "1029c3af85768c4190bb7ad29bc67b5"))
    )
    (comp (ref "R286")
      (value "60.4K")
      (footprint "RESC1005X40X25NL05T05")
      (fields (field (name "PART NUMBER") "CRCW040260K4FKED") (field (name "MANUFACTURER") "Vishay Dale"))
      (libsource (lib "Altium Content Vault") (part "RES"))
    )
    (comp (ref "R287")
      (value "100K")
      (footprint "FP-CRCW0402-e3-IPC_C")
      (description "RES Thick Film, 100kΩ, 1%, 0.063W, 100ppm/°C, 0402")
      (fields (field (name "TOLERANCE") "1%"))
      (libsource (lib "Altium Content Vault") (part "1029c3af85768c4190bb7ad29bc67b5"))
    )
    (comp (ref "R288")
      (value "60.4K")
      (footprint "RESC1005X40X25NL05T05")
      (fields (field (name "PART NUMBER") "CRCW040260K4FKED") (field (name "MANUFACTURER") "Vishay Dale"))
      (libsource (lib "Altium Content Vault") (part "RES"))
    )
    (comp (ref "R289")
      (value "604")
      (footprint "RESC1005X40X25ML05T05")
      (fields (field (name "PART NUMBER") "ERJ-2RKF6040X") (field (name "MANUFACTURER") "Panasonic"))
      (libsource (lib "Altium Content Vault") (part "RES"))
    )
    (comp (ref "R290")
      (value "604")
      (footprint "RESC1005X40X25ML05T05")
      (fields (field (name "PART NUMBER") "ERJ-2RKF6040X") (field (name "MANUFACTURER") "Panasonic"))
      (libsource (lib "Altium Content Vault") (part "RES"))
    )
    (comp (ref "R291")
      (value "0")
      (footprint "FP-CRCW0402-e3-IPC_C")
      (description "RES Thick Film, 0Ω, 0.063W, 0402")
      (fields (field (name "TOLERANCE") "5%"))
      (libsource (lib "Altium Content Vault") (part "1029c3af85768c4190bb7ad29bc67b5"))
    )
    (comp (ref "R292")
      (value "0")
      (footprint "FP-CRCW0402-e3-IPC_C")
      (description "RES Thick Film, 0Ω, 0.063W, 0402")
      (fields (field (name "TOLERANCE") "5%"))
      (libsource (lib "Altium Content Vault") (part "1029c3af85768c4190bb7ad29bc67b5"))
    )
    (comp (ref "R293")
      (value "100K")
      (footprint "FP-CRCW0805-e3-MFG")
      (description "RES Thick Film, 100kΩ, 1%, 0.125W, 100ppm/°C, 0805")
      (fields (field (name "TOLERANCE") "1%"))
      (libsource (lib "Altium Content Vault") (part "1029c3af85768c4190bb7ad29bc67b5"))
    )
    (comp (ref "R294")
      (value "4.7K")
      (footprint "RESC1005X40X25LL05T05")
      (description "Chip Resistor, 4.7 KOhm, +/- 1%, 0.1 W, -55 to 155 degC, 0402 (1005 Metric), RoHS, Tape and Reel")
      (fields (field (name "TOLERANCE") "1%") (field (name "PARTNUMBER") "ERJ-2RKF4701X"))
      (libsource (lib "Altium Content Vault") (part "RES-2"))
    )
    (comp (ref "R295")
      (value "10")
      (footprint "RESC1005X40X25LL05T05")
      (fields (field (name "PART NUMBER") "CRCW040210R0FKED") (field (name "MANUFACTURER") "Vishay Dale"))
      (libsource (lib "Altium Content Vault") (part "RES"))
    )
    (comp (ref "R296")
      (value "10")
      (footprint "RESC1005X40X25LL05T05")
      (fields (field (name "PART NUMBER") "CRCW040210R0FKED") (field (name "MANUFACTURER") "Vishay Dale"))
      (libsource (lib "Altium Content Vault") (part "RES"))
    )
    (comp (ref "R297")
      (value "0.001")
      (footprint "FP-HCS3920FT1L00-MFG")
      (description "RES 0.001 OHM 1% 5W 3920")
      (fields
        (field (name "OCTOPART") "https://octopart.com/hcs3920ft1l00-stackpole+electronics-33343675")
        (field (name "MANUFACTURER PART NUMBER") "HCS3920FT1L00")
      )
      (libsource (lib "Altium Content Vault") (part "1029c3af85768c4190bb7ad29bc67b5"))
    )
    (comp (ref "R298")
      (value "10K")
      (footprint "RESC1005X40X25LL05T05")
      (description "Chip Resistor, 10 KOhm, +/- 1%, 0.1 W, -55 to 155 degC, 0402 (1005 Metric), RoHS, Tape and Reel")
      (fields (field (name "TOLERANCE") "1%") (field (name "MANUFACTURER") "Panasonic"))
      (libsource (lib "Altium Content Vault") (part "RES-2"))
    )
    (comp (ref "R299")
      (value "90.9K")
      (footprint "RESC1005X40X25NL05T05")
      (fields (field (name "PART NUMBER") "ERJ-2RKF90R9X") (field (name "MANUFACTURER") "Panasonic"))
      (libsource (lib "Altium Content Vault") (part "RES"))
    )
    (comp (ref "R300")
      (value "10")
      (footprint "RESC1005X40X25LL05T05")
      (fields (field (name "PART NUMBER") "CRCW040210R0FKED") (field (name "MANUFACTURER") "Vishay Dale"))
      (libsource (lib "Altium Content Vault") (part "RES"))
    )
    (comp (ref "R301")
      (value "10")
      (footprint "RESC1005X40X25LL05T05")
      (fields (field (name "PART NUMBER") "CRCW040210R0FKED") (field (name "MANUFACTURER") "Vishay Dale"))
      (libsource (lib "Altium Content Vault") (part "RES"))
    )
    (comp (ref "R302")
      (value "10")
      (footprint "RESC1005X40X25LL05T05")
      (fields (field (name "PART NUMBER") "CRCW040210R0FKED") (field (name "MANUFACTURER") "Vishay Dale"))
      (libsource (lib "Altium Content Vault") (part "RES"))
    )
    (comp (ref "R303")
      (value "13.3k")
      (footprint "RESC1005X40X25ML05T05")
      (fields (field (name "MANUFACTURER") "Vishay Dale") (field (name "PART NUMBER") "CRCW040213K3FKED"))
      (libsource (lib "Altium Content Vault") (part "RES"))
    )
    (comp (ref "R304")
      (value "3.24K")
      (footprint "RESC2013X70X40ML20T20")
      (fields (field (name "MANUFACTURER") "Panasonic") (field (name "PART NUMBER") "ERJ-6ENF3241V"))
      (libsource (lib "Altium Content Vault") (part "RES"))
    )
    (comp (ref "R305")
      (value "8.25K")
      (footprint "RESC1609X50X30NL10T20")
      (fields (field (name "MANUFACTURER") "Vishay Dale") (field (name "PART NUMBER") "CRCW06038K25FKEA"))
      (libsource (lib "Altium Content Vault") (part "RES"))
    )
    (comp (ref "R306")
      (value "120K")
      (footprint "RESC1005X40X25NL05T05")
      (fields (field (name "PART NUMBER") "CRCW0402120KFKED") (field (name "MANUFACTURER") "Vishay Dale"))
      (libsource (lib "Altium Content Vault") (part "RES"))
    )
    (comp (ref "R307")
      (value "121K")
      (footprint "FP-CRCW0402-e3-MFG")
      (description "RES Thick Film, 121kΩ, 1%, 0.063W, 100ppm/°C, 0402")
      (fields (field (name "TOLERANCE") "1%"))
      (libsource (lib "Altium Content Vault") (part "1029c3af85768c4190bb7ad29bc67b5"))
    )
    (comp (ref "U6")
      (value "SN74AUC1G07DCKT")
      (footprint "DCK0005A_M")
      (description "Single Buffer/Driver With Open-Drain Output, DCK0005A, SMALL T&R")
      (fields
        (field (name "MANUFACTURER") "Texas Instruments")
        (field (name "GENERIC PART NUMBER") "SN74AUC1G07")
      )
      (libsource (lib "Altium Content Vault") (part "TI-SN74XXX1G07-5"))
    )
    (comp (ref "U7")
      (value "SN74AUC1G07DCKT")
      (footprint "DCK0005A_M")
      (description "Single Buffer/Driver With Open-Drain Output, DCK0005A, SMALL T&R")
      (fields
        (field (name "MANUFACTURER") "Texas Instruments")
        (field (name "GENERIC PART NUMBER") "SN74AUC1G07")
      )
      (libsource (lib "Altium Content Vault") (part "TI-SN74XXX1G07-5"))
    )
  )
  (nets
    (net (code "1") (name "+2V5") (class "Default")
      (node (ref "C593") (pin "1") (pinfunction "1_1") (pintype "passive"))
      (node (ref "C594") (pin "2") (pinfunction "2_2") (pintype "passive"))
      (node (ref "C595") (pin "1") (pinfunction "1_1") (pintype "passive"))
      (node (ref "C596") (pin "1") (pinfunction "1_1") (pintype "passive"))
      (node (ref "IC31") (pin "9") (pinfunction "VFB_9") (pintype "passive"))
      (node (ref "IC32") (pin "10") (pinfunction "OUT_2_10") (pintype "passive"))
      (node (ref "IC32") (pin "9") (pinfunction "OUT_1_9") (pintype "passive"))
      (node (ref "R275") (pin "2") (pinfunction "2_2") (pintype "passive"))
      (node (ref "R277") (pin "2") (pinfunction "2_2") (pintype "passive"))
    )
    (net (code "2") (name "+3V3") (class "Default")
      (node (ref "C602") (pin "1") (pinfunction "1_1") (pintype "passive"))
      (node (ref "C603") (pin "1") (pinfunction "1_1") (pintype "passive"))
      (node (ref "C606") (pin "1") (pinfunction "1_1") (pintype "passive"))
      (node (ref "C607") (pin "1") (pinfunction "1_1") (pintype "passive"))
      (node (ref "C610") (pin "2") (pinfunction "2_2") (pintype "passive"))
      (node (ref "C611") (pin "2") (pinfunction "2_2") (pintype "passive"))
      (node (ref "C620") (pin "2") (pinfunction "2_2") (pintype "passive"))
      (node (ref "C628") (pin "1") (pinfunction "1_1") (pintype "passive"))
      (node (ref "C629") (pin "2") (pinfunction "2_2") (pintype "passive"))
      (node (ref "IC32") (pin "1") (pinfunction "IN_1_1") (pintype "passive"))
      (node (ref "IC32") (pin "2") (pinfunction "IN_2_2") (pintype "passive"))
      (node (ref "IC33") (pin "1") (pinfunction "IN_1_1") (pintype "passive"))
      (node (ref "IC33") (pin "2") (pinfunction "IN_2_2") (pintype "passive"))
      (node (ref "IC33") (pin "3") (pinfunction "~{SHDN}_3") (pintype "passive"))
      (node (ref "IC34") (pin "6") (pinfunction "VS_6") (pintype "passive"))
      (node (ref "IC36") (pin "A1") (pinfunction "VOUT1_1_A1") (pintype "passive"))
      (node (ref "IC36") (pin "A2") (pinfunction "VOUT1_2_A2") (pintype "passive"))
      (node (ref "IC36") (pin "A3") (pinfunction "VOUT1_3_A3") (pintype "passive"))
      (node (ref "IC36") (pin "A4") (pinfunction "VOUT1_4_A4") (pintype "passive"))
      (node (ref "IC36") (pin "A5") (pinfunction "VOUT1_5_A5") (pintype "passive"))
      (node (ref "IC36") (pin "B1") (pinfunction "VOUT1_6_B1") (pintype "passive"))
      (node (ref "IC36") (pin "B2") (pinfunction "VOUT1_7_B2") (pintype "passive"))
      (node (ref "IC36") (pin "B3") (pinfunction "VOUT1_8_B3") (pintype "passive"))
      (node (ref "IC36") (pin "B4") (pinfunction "VOUT1_9_B4") (pintype "passive"))
      (node (ref "IC36") (pin "B5") (pinfunction "VOUT1_10_B5") (pintype "passive"))
      (node (ref "IC36") (pin "C1") (pinfunction "VOUT1_11_C1") (pintype "passive"))
      (node (ref "IC36") (pin "C2") (pinfunction "VOUT1_12_C2") (pintype "passive"))
      (node (ref "IC36") (pin "C3") (pinfunction "VOUT1_13_C3") (pintype "passive"))
      (node (ref "IC36") (pin "C4") (pinfunction "VOUT1_14_C4") (pintype "passive"))
      (node (ref "IC36") (pin "C5") (pinfunction "VOUTS1_C5") (pintype "passive"))
      (node (ref "IC36") (pin "E6") (pinfunction "COMP1_E6") (pintype "passive"))
      (node (ref "IC36") (pin "F8") (pinfunction "DIFFOUT_F8") (pintype "passive"))
      (node (ref "R281") (pin "2") (pinfunction "2_2") (pintype "passive"))
      (node (ref "R285") (pin "2") (pinfunction "2_2") (pintype "passive"))
      (node (ref "R287") (pin "2") (pinfunction "2_2") (pintype "passive"))
      (node (ref "U6") (pin "5") (pinfunction "VCC_5") (pintype "power_in"))
      (node (ref "U7") (pin "5") (pinfunction "VCC_5") (pintype "power_in"))
    )
    (net (code "3") (name "+5V") (class "Default")
      (node (ref "C598") (pin "1") (pinfunction "1_1") (pintype "passive"))
      (node (ref "C599") (pin "2") (pinfunction "2_2") (pintype "passive"))
      (node (ref "C644") (pin "1") (pinfunction "1_1") (pintype "passive"))
      (node (ref "C645") (pin "2") (pinfunction "2_2") (pintype "passive"))
      (node (ref "IC31") (pin "2") (pinfunction "SYNC/MODE_2") (pintype "passive"))
      (node (ref "IC31") (pin "6") (pinfunction "PVIN_6") (pintype "passive"))
      (node (ref "IC31") (pin "7") (pinfunction "SVIN_7") (pintype "passive"))
      (node (ref "IC36") (pin "A10") (pinfunction "VOUT2_3_A10") (pintype "passive"))
      (node (ref "IC36") (pin "A11") (pinfunction "VOUT2_4_A11") (pintype "passive"))
      (node (ref "IC36") (pin "A12") (pinfunction "VOUT2_5_A12") (pintype "passive"))
      (node (ref "IC36") (pin "A8") (pinfunction "VOUT2_1_A8") (pintype "passive"))
      (node (ref "IC36") (pin "A9") (pinfunction "VOUT2_2_A9") (pintype "passive"))
      (node (ref "IC36") (pin "B10") (pinfunction "VOUT2_8_B10") (pintype "passive"))
      (node (ref "IC36") (pin "B11") (pinfunction "VOUT2_9_B11") (pintype "passive"))
      (node (ref "IC36") (pin "B12") (pinfunction "VOUT2_10_B12") (pintype "passive"))
      (node (ref "IC36") (pin "B8") (pinfunction "VOUT2_6_B8") (pintype "passive"))
      (node (ref "IC36") (pin "B9") (pinfunction "VOUT2_7_B9") (pintype "passive"))
      (node (ref "IC36") (pin "C10") (pinfunction "VOUT2_12_C10") (pintype "passive"))
      (node (ref "IC36") (pin "C11") (pinfunction "VOUT2_13_C11") (pintype "passive"))
      (node (ref "IC36") (pin "C12") (pinfunction "VOUT2_14_C12") (pintype "passive"))
      (node (ref "IC36") (pin "C8") (pinfunction "VOUTS2_C8") (pintype "passive"))
      (node (ref "IC36") (pin "C9") (pinfunction "VOUT2_11_C9") (pintype "passive"))
      (node (ref "IC36") (pin "E7") (pinfunction "COMP2_E7") (pintype "passive"))
    )
    (net (code "4") (name "+12") (class "Default")
      (node (ref "C614") (pin "1") (pinfunction "1_1") (pintype "passive"))
      (node (ref "C614") (pin "2") (pinfunction "2_2") (pintype "passive"))
      (node (ref "C615") (pin "1") (pinfunction "1_1") (pintype "passive"))
      (node (ref "C615") (pin "2") (pinfunction "2_2") (pintype "passive"))
      (node (ref "C616") (pin "1") (pinfunction "1_1") (pintype "passive"))
      (node (ref "C616") (pin "2") (pinfunction "2_2") (pintype "passive"))
      (node (ref "C617") (pin "1") (pinfunction "1_1") (pintype "passive"))
      (node (ref "C617") (pin "2") (pinfunction "2_2") (pintype "passive"))
      (node (ref "C619") (pin "1") (pinfunction "1_1") (pintype "passive"))
      (node (ref "C619") (pin "2") (pinfunction "2_2") (pintype "passive"))
      (node (ref "L38") (pin "2") (pinfunction "2_2") (pintype "passive"))
      (node (ref "Q2") (pin "5") (pinfunction "D_1_5") (pintype "passive"))
      (node (ref "Q2") (pin "6") (pinfunction "D_2_6") (pintype "passive"))
      (node (ref "Q2") (pin "7") (pinfunction "D_3_7") (pintype "passive"))
      (node (ref "Q2") (pin "8") (pinfunction "D_4_8") (pintype "passive"))
      (node (ref "Q2") (pin "9") (pinfunction "D_5_9") (pintype "passive"))
    )
    (net (code "5") (name "+12V") (class "Default")
      (node (ref "C630") (pin "1") (pinfunction "1_1") (pintype "passive"))
      (node (ref "C631") (pin "1") (pinfunction "1_1") (pintype "passive"))
      (node (ref "C632") (pin "1") (pinfunction "1_1") (pintype "passive"))
      (node (ref "C633") (pin "1") (pinfunction "1_1") (pintype "passive"))
      (node (ref "C634") (pin "1") (pinfunction "1_1") (pintype "passive"))
      (node (ref "C635") (pin "1") (pinfunction "1_1") (pintype "passive"))
      (node (ref "C636") (pin "1") (pinfunction "1_1") (pintype "passive"))
      (node (ref "C637") (pin "1") (pinfunction "1_1") (pintype "passive"))
      (node (ref "IC35") (pin "J10") (pinfunction "VIN_5_J10") (pintype "passive"))
      (node (ref "IC35") (pin "J11") (pinfunction "VIN_6_J11") (pintype "passive"))
      (node (ref "IC35") (pin "J2") (pinfunction "VIN_1_J2") (pintype "passive"))
      (node (ref "IC35") (pin "J3") (pinfunction "VIN_2_J3") (pintype "passive"))
      (node (ref "IC35") (pin "J4") (pinfunction "VIN_3_J4") (pintype "passive"))
      (node (ref "IC35") (pin "J9") (pinfunction "VIN_4_J9") (pintype "passive"))
      (node (ref "IC35") (pin "K10") (pinfunction "VIN_11_K10") (pintype "passive"))
      (node (ref "IC35") (pin "K11") (pinfunction "VIN_12_K11") (pintype "passive"))
      (node (ref "IC35") (pin "K2") (pinfunction "VIN_7_K2") (pintype "passive"))
      (node (ref "IC35") (pin "K3") (pinfunction "VIN_8_K3") (pintype "passive"))
      (node (ref "IC35") (pin "K4") (pinfunction "VIN_9_K4") (pintype "passive"))
      (node (ref "IC35") (pin "K9") (pinfunction "VIN_10_K9") (pintype "passive"))
      (node (ref "IC35") (pin "L10") (pinfunction "VIN_21_L10") (pintype "passive"))
      (node (ref "IC35") (pin "L11") (pinfunction "VIN_22_L11") (pintype "passive"))
      (node (ref "IC35") (pin "L2") (pinfunction "VIN_13_L2") (pintype "passive"))
      (node (ref "IC35") (pin "L3") (pinfunction "VIN_14_L3") (pintype "passive"))
      (node (ref "IC35") (pin "L4") (pinfunction "VIN_15_L4") (pintype "passive"))
      (node (ref "IC35") (pin "L5") (pinfunction "VIN_16_L5") (pintype "passive"))
      (node (ref "IC35") (pin "L6") (pinfunction "VIN_17_L6") (pintype "passive"))
      (node (ref "IC35") (pin "L7") (pinfunction "VIN_18_L7") (pintype "passive"))
      (node (ref "IC35") (pin "L8") (pinfunction "VIN_19_L8") (pintype "passive"))
      (node (ref "IC35") (pin "L9") (pinfunction "VIN_20_L9") (pintype "passive"))
      (node (ref "IC35") (pin "M10") (pinfunction "VIN_31_M10") (pintype "passive"))
      (node (ref "IC35") (pin "M11") (pinfunction "VIN_32_M11") (pintype "passive"))
      (node (ref "IC35") (pin "M2") (pinfunction "VIN_23_M2") (pintype "passive"))
      (node (ref "IC35") (pin "M3") (pinfunction "VIN_24_M3") (pintype "passive"))
      (node (ref "IC35") (pin "M4") (pinfunction "VIN_25_M4") (pintype "passive"))
      (node (ref "IC35") (pin "M5") (pinfunction "VIN_26_M5") (pintype "passive"))
      (node (ref "IC35") (pin "M6") (pinfunction "VIN_27_M6") (pintype "passive"))
      (node (ref "IC35") (pin "M7") (pinfunction "VIN_28_M7") (pintype "passive"))
      (node (ref "IC35") (pin "M8") (pinfunction "VIN_29_M8") (pintype "passive"))
      (node (ref "IC35") (pin "M9") (pinfunction "VIN_30_M9") (pintype "passive"))
      (node (ref "IC36") (pin "J10") (pinfunction "VIN_5_J10") (pintype "passive"))
      (node (ref "IC36") (pin "J11") (pinfunction "VIN_6_J11") (pintype "passive"))
      (node (ref "IC36") (pin "J2") (pinfunction "VIN_1_J2") (pintype "passive"))
      (node (ref "IC36") (pin "J3") (pinfunction "VIN_2_J3") (pintype "passive"))
      (node (ref "IC36") (pin "J4") (pinfunction "VIN_3_J4") (pintype "passive"))
      (node (ref "IC36") (pin "J9") (pinfunction "VIN_4_J9") (pintype "passive"))
      (node (ref "IC36") (pin "K10") (pinfunction "VIN_11_K10") (pintype "passive"))
      (node (ref "IC36") (pin "K11") (pinfunction "VIN_12_K11") (pintype "passive"))
      (node (ref "IC36") (pin "K2") (pinfunction "VIN_7_K2") (pintype "passive"))
      (node (ref "IC36") (pin "K3") (pinfunction "VIN_8_K3") (pintype "passive"))
      (node (ref "IC36") (pin "K4") (pinfunction "VIN_9_K4") (pintype "passive"))
      (node (ref "IC36") (pin "K9") (pinfunction "VIN_10_K9") (pintype "passive"))
      (node (ref "IC36") (pin "L10") (pinfunction "VIN_21_L10") (pintype "passive"))
      (node (ref "IC36") (pin "L11") (pinfunction "VIN_22_L11") (pintype "passive"))
      (node (ref "IC36") (pin "L2") (pinfunction "VIN_13_L2") (pintype "passive"))
      (node (ref "IC36") (pin "L3") (pinfunction "VIN_14_L3") (pintype "passive"))
      (node (ref "IC36") (pin "L4") (pinfunction "VIN_15_L4") (pintype "passive"))
      (node (ref "IC36") (pin "L5") (pinfunction "VIN_16_L5") (pintype "passive"))
      (node (ref "IC36") (pin "L6") (pinfunction "VIN_17_L6") (pintype "passive"))
      (node (ref "IC36") (pin "L7") (pinfunction "VIN_18_L7") (pintype "passive"))
      (node (ref "IC36") (pin "L8") (pinfunction "VIN_19_L8") (pintype "passive"))
      (node (ref "IC36") (pin "L9") (pinfunction "VIN_20_L9") (pintype "passive"))
      (node (ref "IC36") (pin "M10") (pinfunction "VIN_31_M10") (pintype "passive"))
      (node (ref "IC36") (pin "M11") (pinfunction "VIN_32_M11") (pintype "passive"))
      (node (ref "IC36") (pin "M2") (pinfunction "VIN_23_M2") (pintype "passive"))
      (node (ref "IC36") (pin "M3") (pinfunction "VIN_24_M3") (pintype "passive"))
      (node (ref "IC36") (pin "M4") (pinfunction "VIN_25_M4") (pintype "passive"))
      (node (ref "IC36") (pin "M5") (pinfunction "VIN_26_M5") (pintype "passive"))
      (node (ref "IC36") (pin "M6") (pinfunction "VIN_27_M6") (pintype "passive"))
      (node (ref "IC36") (pin "M7") (pinfunction "VIN_28_M7") (pintype "passive"))
      (node (ref "IC36") (pin "M8") (pinfunction "VIN_29_M8") (pintype "passive"))
      (node (ref "IC36") (pin "M9") (pinfunction "VIN_30_M9") (pintype "passive"))
      (node (ref "R306") (pin "1") (pinfunction "1_1") (pintype "passive"))
    )
    (net (code "6") (name "+CPU_VDD") (class "Default")
      (node (ref "R296") (pin "1") (pinfunction "1_1") (pintype "passive"))
      (node (ref "R297") (pin "2") (pinfunction "2_2") (pintype "passive"))
    )
    (net (code "7") (name "+CPU_VDD_I") (class "Default")
      (node (ref "C622") (pin "2") (pinfunction "2_2") (pintype "passive"))
      (node (ref "C623") (pin "2") (pinfunction "2_2") (pintype "passive"))
      (node (ref "C624") (pin "2") (pinfunction "2_2") (pintype "passive"))
      (node (ref "C625") (pin "2") (pinfunction "2_2") (pintype "passive"))
      (node (ref "C626") (pin "2") (pinfunction "2_2") (pintype "passive"))
      (node (ref "C627") (pin "2") (pinfunction "2_2") (pintype "passive"))
      (node (ref "IC35") (pin "A1") (pinfunction "VOUT1_1_A1") (pintype "passive"))
      (node (ref "IC35") (pin "A10") (pinfunction "VOUT2_3_A10") (pintype "passive"))
      (node (ref "IC35") (pin "A11") (pinfunction "VOUT2_4_A11") (pintype "passive"))
      (node (ref "IC35") (pin "A12") (pinfunction "VOUT2_5_A12") (pintype "passive"))
      (node (ref "IC35") (pin "A2") (pinfunction "VOUT1_2_A2") (pintype "passive"))
      (node (ref "IC35") (pin "A3") (pinfunction "VOUT1_3_A3") (pintype "passive"))
      (node (ref "IC35") (pin "A4") (pinfunction "VOUT1_4_A4") (pintype "passive"))
      (node (ref "IC35") (pin "A5") (pinfunction "VOUT1_5_A5") (pintype "passive"))
      (node (ref "IC35") (pin "A8") (pinfunction "VOUT2_1_A8") (pintype "passive"))
      (node (ref "IC35") (pin "A9") (pinfunction "VOUT2_2_A9") (pintype "passive"))
      (node (ref "IC35") (pin "B1") (pinfunction "VOUT1_6_B1") (pintype "passive"))
      (node (ref "IC35") (pin "B10") (pinfunction "VOUT2_8_B10") (pintype "passive"))
      (node (ref "IC35") (pin "B11") (pinfunction "VOUT2_9_B11") (pintype "passive"))
      (node (ref "IC35") (pin "B12") (pinfunction "VOUT2_10_B12") (pintype "passive"))
      (node (ref "IC35") (pin "B2") (pinfunction "VOUT1_7_B2") (pintype "passive"))
      (node (ref "IC35") (pin "B3") (pinfunction "VOUT1_8_B3") (pintype "passive"))
      (node (ref "IC35") (pin "B4") (pinfunction "VOUT1_9_B4") (pintype "passive"))
      (node (ref "IC35") (pin "B5") (pinfunction "VOUT1_10_B5") (pintype "passive"))
      (node (ref "IC35") (pin "B8") (pinfunction "VOUT2_6_B8") (pintype "passive"))
      (node (ref "IC35") (pin "B9") (pinfunction "VOUT2_7_B9") (pintype "passive"))
      (node (ref "IC35") (pin "C1") (pinfunction "VOUT1_11_C1") (pintype "passive"))
      (node (ref "IC35") (pin "C10") (pinfunction "VOUT2_12_C10") (pintype "passive"))
      (node (ref "IC35") (pin "C11") (pinfunction "VOUT2_13_C11") (pintype "passive"))
      (node (ref "IC35") (pin "C12") (pinfunction "VOUT2_14_C12") (pintype "passive"))
      (node (ref "IC35") (pin "C2") (pinfunction "VOUT1_12_C2") (pintype "passive"))
      (node (ref "IC35") (pin "C3") (pinfunction "VOUT1_13_C3") (pintype "passive"))
      (node (ref "IC35") (pin "C4") (pinfunction "VOUT1_14_C4") (pintype "passive"))
      (node (ref "IC35") (pin "C8") (pinfunction "VOUTS2_C8") (pintype "passive"))
      (node (ref "IC35") (pin "C9") (pinfunction "VOUT2_11_C9") (pintype "passive"))
      (node (ref "IC35") (pin "E6") (pinfunction "COMP1_E6") (pintype "passive"))
      (node (ref "IC35") (pin "E7") (pinfunction "COMP2_E7") (pintype "passive"))
      (node (ref "R295") (pin "1") (pinfunction "1_1") (pintype "passive"))
      (node (ref "R297") (pin "1") (pinfunction "1_1") (pintype "passive"))
      (node (ref "R301") (pin "2") (pinfunction "2_2") (pintype "passive"))
      (node (ref "R304") (pin "2") (pinfunction "2_2") (pintype "passive"))
    )
    (net (code "8") (name "/CPU_GND_SENSE") (class "Default")
      (node (ref "IC35") (pin "E9") (pinfunction "DIFFN_E9") (pintype "passive"))
      (node (ref "IC36") (pin "E9") (pinfunction "DIFFN_E9") (pintype "passive"))
      (node (ref "R300") (pin "1") (pinfunction "1_1") (pintype "passive"))
    )
    (net (code "9") (name "/CPU_VDD_SENSE") (class "Default")
      (node (ref "IC35") (pin "E8") (pinfunction "DIFFP_E8") (pintype "passive"))
      (node (ref "IC36") (pin "E8") (pinfunction "DIFFP_E8") (pintype "passive"))
      (node (ref "R301") (pin "1") (pinfunction "1_1") (pintype "passive"))
    )
    (net (code "10") (name "/I2C1_SCL") (class "Default")
      (node (ref "IC34") (pin "5") (pinfunction "SCL_5") (pintype "passive"))
    )
    (net (code "11") (name "/I2C1_SDA") (class "Default")
      (node (ref "IC34") (pin "4") (pinfunction "SDA_4") (pintype "passive"))
    )
    (net (code "12") (name "/INA_VDD_S_N") (class "Default")
      (node (ref "C621") (pin "1") (pinfunction "1_1") (pintype "passive"))
      (node (ref "IC34") (pin "9") (pinfunction "VIN-_9") (pintype "passive"))
      (node (ref "R296") (pin "2") (pinfunction "2_2") (pintype "passive"))
    )
    (net (code "13") (name "/INA_VDD_S_P") (class "Default")
      (node (ref "C621") (pin "2") (pinfunction "2_2") (pintype "passive"))
      (node (ref "IC34") (pin "10") (pinfunction "VIN+_10") (pintype "passive"))
      (node (ref "R295") (pin "2") (pinfunction "2_2") (pintype "passive"))
    )
    (net (code "14") (name "/PWR_SW") (class "Default")
      (node (ref "P10") (pin "2") (pinfunction "2_2") (pintype "passive"))
      (node (ref "R294") (pin "1") (pinfunction "1_1") (pintype "passive"))
    )
    (net (code "15") (name "/S1VDD_PG") (class "Default")
      (node (ref "R292") (pin "1") (pinfunction "1_1") (pintype "passive"))
    )
    (net (code "16") (name "/TVDD_PG") (class "Default")
      (node (ref "R291") (pin "1") (pinfunction "1_1") (pintype "passive"))
    )
    (net (code "17") (name "EN_+VDD") (class "Default")
      (node (ref "IC35") (pin "F5") (pinfunction "RUN1_F5") (pintype "passive"))
      (node (ref "IC35") (pin "F9") (pinfunction "RUN2_F9") (pintype "passive"))
      (node (ref "IC36") (pin "F5") (pinfunction "RUN1_F5") (pintype "passive"))
      (node (ref "IC36") (pin "F9") (pinfunction "RUN2_F9") (pintype "passive"))
    )
    (net (code "18") (name "GND") (class "Default")
      (node (ref "C596") (pin "2") (pinfunction "2_2") (pintype "passive"))
      (node (ref "C597") (pin "2") (pinfunction "2_2") (pintype "passive"))
      (node (ref "C598") (pin "2") (pinfunction "2_2") (pintype "passive"))
      (node (ref "C599") (pin "1") (pinfunction "1_1") (pintype "passive"))
      (node (ref "C600") (pin "1") (pinfunction "1_1") (pintype "passive"))
      (node (ref "C601") (pin "1") (pinfunction "1_1") (pintype "passive"))
      (node (ref "C602") (pin "2") (pinfunction "2_2") (pintype "passive"))
      (node (ref "C603") (pin "2") (pinfunction "2_2") (pintype "passive"))
      (node (ref "C604") (pin "2") (pinfunction "2_2") (pintype "passive"))
      (node (ref "C605") (pin "2") (pinfunction "2_2") (pintype "passive"))
      (node (ref "C606") (pin "2") (pinfunction "2_2") (pintype "passive"))
      (node (ref "C607") (pin "2") (pinfunction "2_2") (pintype "passive"))
      (node (ref "C608") (pin "2") (pinfunction "2_2") (pintype "passive"))
      (node (ref "C609") (pin "2") (pinfunction "2_2") (pintype "passive"))
      (node (ref "C610") (pin "1") (pinfunction "1_1") (pintype "passive"))
      (node (ref "C611") (pin "1") (pinfunction "1_1") (pintype "passive"))
      (node (ref "C620") (pin "1") (pinfunction "1_1") (pintype "passive"))
      (node (ref "C622") (pin "1") (pinfunction "1_1") (pintype "passive"))
      (node (ref "C623") (pin "1") (pinfunction "1_1") (pintype "passive"))
      (node (ref "C624") (pin "1") (pinfunction "1_1") (pintype "passive"))
      (node (ref "C625") (pin "1") (pinfunction "1_1") (pintype "passive"))
      (node (ref "C626") (pin "1") (pinfunction "1_1") (pintype "passive"))
      (node (ref "C627") (pin "1") (pinfunction "1_1") (pintype "passive"))
      (node (ref "C628") (pin "2") (pinfunction "2_2") (pintype "passive"))
      (node (ref "C629") (pin "1") (pinfunction "1_1") (pintype "passive"))
      (node (ref "C630") (pin "2") (pinfunction "2_2") (pintype "passive"))
      (node (ref "C631") (pin "2") (pinfunction "2_2") (pintype "passive"))
      (node (ref "C632") (pin "2") (pinfunction "2_2") (pintype "passive"))
      (node (ref "C633") (pin "2") (pinfunction "2_2") (pintype "passive"))
      (node (ref "C634") (pin "2") (pinfunction "2_2") (pintype "passive"))
      (node (ref "C635") (pin "2") (pinfunction "2_2") (pintype "passive"))
      (node (ref "C636") (pin "2") (pinfunction "2_2") (pintype "passive"))
      (node (ref "C637") (pin "2") (pinfunction "2_2") (pintype "passive"))
      (node (ref "C638") (pin "1") (pinfunction "1_1") (pintype "passive"))
      (node (ref "C640") (pin "2") (pinfunction "2_2") (pintype "passive"))
      (node (ref "C641") (pin "1") (pinfunction "1_1") (pintype "passive"))
      (node (ref "C642") (pin "2") (pinfunction "2_2") (pintype "passive"))
      (node (ref "C643") (pin "2") (pinfunction "2_2") (pintype "passive"))
      (node (ref "C644") (pin "2") (pinfunction "2_2") (pintype "passive"))
      (node (ref "C645") (pin "1") (pinfunction "1_1") (pintype "passive"))
      (node (ref "IC31") (pin "11") (pinfunction "EP_11") (pintype "passive"))
      (node (ref "IC31") (pin "3") (pinfunction "SGND_3") (pintype "passive"))
      (node (ref "IC31") (pin "5") (pinfunction "PGND_5") (pintype "passive"))
      (node (ref "IC32") (pin "11") (pinfunction "EP_11") (pintype "passive"))
      (node (ref "IC32") (pin "7") (pinfunction "GND_7") (pintype "passive"))
      (node (ref "IC33") (pin "11") (pinfunction "EP_11") (pintype "passive"))
      (node (ref "IC33") (pin "7") (pinfunction "GND_7") (pintype "passive"))
      (node (ref "IC34") (pin "1") (pinfunction "A1_1") (pintype "passive"))
      (node (ref "IC34") (pin "2") (pinfunction "A0_2") (pintype "passive"))
      (node (ref "IC34") (pin "7") (pinfunction "GND_7") (pintype "passive"))
      (node (ref "IC35") (pin "A6") (pinfunction "GND_1_A6") (pintype "passive"))
      (node (ref "IC35") (pin "A7") (pinfunction "GND_2_A7") (pintype "passive"))
      (node (ref "IC35") (pin "B6") (pinfunction "GND_3_B6") (pintype "passive"))
      (node (ref "IC35") (pin "B7") (pinfunction "GND_4_B7") (pintype "passive"))
      (node (ref "IC35") (pin "C7") (pinfunction "SGND_1_C7") (pintype "passive"))
      (node (ref "IC35") (pin "D1") (pinfunction "GND_5_D1") (pintype "passive"))
      (node (ref "IC35") (pin "D10") (pinfunction "GND_10_D10") (pintype "passive"))
      (node (ref "IC35") (pin "D11") (pinfunction "GND_11_D11") (pintype "passive"))
      (node (ref "IC35") (pin "D12") (pinfunction "GND_12_D12") (pintype "passive"))
      (node (ref "IC35") (pin "D2") (pinfunction "GND_6_D2") (pintype "passive"))
      (node (ref "IC35") (pin "D3") (pinfunction "GND_7_D3") (pintype "passive"))
      (node (ref "IC35") (pin "D4") (pinfunction "GND_8_D4") (pintype "passive"))
      (node (ref "IC35") (pin "D6") (pinfunction "SGND_2_D6") (pintype "passive"))
      (node (ref "IC35") (pin "D9") (pinfunction "GND_9_D9") (pintype "passive"))
      (node (ref "IC35") (pin "E1") (pinfunction "GND_13_E1") (pintype "passive"))
      (node (ref "IC35") (pin "E10") (pinfunction "GND_17_E10") (pintype "passive"))
      (node (ref "IC35") (pin "E11") (pinfunction "GND_18_E11") (pintype "passive"))
      (node (ref "IC35") (pin "E12") (pinfunction "GND_19_E12") (pintype "passive"))
      (node (ref "IC35") (pin "E2") (pinfunction "GND_14_E2") (pintype "passive"))
      (node (ref "IC35") (pin "E3") (pinfunction "GND_15_E3") (pintype "passive"))
      (node (ref "IC35") (pin "E4") (pinfunction "GND_16_E4") (pintype "passive"))
      (node (ref "IC35") (pin "F1") (pinfunction "GND_20_F1") (pintype "passive"))
      (node (ref "IC35") (pin "F10") (pinfunction "GND_23_F10") (pintype "passive"))
      (node (ref "IC35") (pin "F11") (pinfunction "GND_24_F11") (pintype "passive"))
      (node (ref "IC35") (pin "F12") (pinfunction "GND_25_F12") (pintype "passive"))
      (node (ref "IC35") (pin "F2") (pinfunction "GND_21_F2") (pintype "passive"))
      (node (ref "IC35") (pin "F3") (pinfunction "GND_22_F3") (pintype "passive"))
      (node (ref "IC35") (pin "F4") (pinfunction "MODE_PLLIN_F4") (pintype "passive"))
      (node (ref "IC35") (pin "F6") (pinfunction "SGND_3_F6") (pintype "passive"))
      (node (ref "IC35") (pin "F7") (pinfunction "SGND_4_F7") (pintype "passive"))
      (node (ref "IC35") (pin "G1") (pinfunction "GND_26_G1") (pintype "passive"))
      (node (ref "IC35") (pin "G10") (pinfunction "GND_28_G10") (pintype "passive"))
      (node (ref "IC35") (pin "G12") (pinfunction "GND_29_G12") (pintype "passive"))
      (node (ref "IC35") (pin "G3") (pinfunction "GND_27_G3") (pintype "passive"))
      (node (ref "IC35") (pin "G4") (pinfunction "PHASMD_G4") (pintype "passive"))
      (node (ref "IC35") (pin "G6") (pinfunction "SGND_5_G6") (pintype "passive"))
      (node (ref "IC35") (pin "G7") (pinfunction "SGND_6_G7") (pintype "passive"))
      (node (ref "IC35") (pin "H1") (pinfunction "GND_30_H1") (pintype "passive"))
      (node (ref "IC35") (pin "H10") (pinfunction "GND_38_H10") (pintype "passive"))
      (node (ref "IC35") (pin "H11") (pinfunction "GND_39_H11") (pintype "passive"))
      (node (ref "IC35") (pin "H12") (pinfunction "GND_40_H12") (pintype "passive"))
      (node (ref "IC35") (pin "H2") (pinfunction "GND_31_H2") (pintype "passive"))
      (node (ref "IC35") (pin "H3") (pinfunction "GND_32_H3") (pintype "passive"))
      (node (ref "IC35") (pin "H4") (pinfunction "GND_33_H4") (pintype "passive"))
      (node (ref "IC35") (pin "H5") (pinfunction "GND_34_H5") (pintype "passive"))
      (node (ref "IC35") (pin "H6") (pinfunction "GND_35_H6") (pintype "passive"))
      (node (ref "IC35") (pin "H7") (pinfunction "GND_36_H7") (pintype "passive"))
      (node (ref "IC35") (pin "H9") (pinfunction "GND_37_H9") (pintype "passive"))
      (node (ref "IC35") (pin "J1") (pinfunction "GND_41_J1") (pintype "passive"))
      (node (ref "IC35") (pin "J12") (pinfunction "GND_44_J12") (pintype "passive"))
      (node (ref "IC35") (pin "J5") (pinfunction "GND_42_J5") (pintype "passive"))
      (node (ref "IC35") (pin "J8") (pinfunction "GND_43_J8") (pintype "passive"))
      (node (ref "IC35") (pin "K1") (pinfunction "GND_45_K1") (pintype "passive"))
      (node (ref "IC35") (pin "K12") (pinfunction "GND_50_K12") (pintype "passive"))
      (node (ref "IC35") (pin "K5") (pinfunction "GND_46_K5") (pintype "passive"))
      (node (ref "IC35") (pin "K6") (pinfunction "GND_47_K6") (pintype "passive"))
      (node (ref "IC35") (pin "K7") (pinfunction "GND_48_K7") (pintype "passive"))
      (node (ref "IC35") (pin "K8") (pinfunction "GND_49_K8") (pintype "passive"))
      (node (ref "IC35") (pin "L1") (pinfunction "GND_51_L1") (pintype "passive"))
      (node (ref "IC35") (pin "L12") (pinfunction "GND_52_L12") (pintype "passive"))
      (node (ref "IC35") (pin "M1") (pinfunction "GND_53_M1") (pintype "passive"))
      (node (ref "IC35") (pin "M12") (pinfunction "GND_54_M12") (pintype "passive"))
      (node (ref "IC36") (pin "A6") (pinfunction "GND_1_A6") (pintype "passive"))
      (node (ref "IC36") (pin "A7") (pinfunction "GND_2_A7") (pintype "passive"))
      (node (ref "IC36") (pin "B6") (pinfunction "GND_3_B6") (pintype "passive"))
      (node (ref "IC36") (pin "B7") (pinfunction "GND_4_B7") (pintype "passive"))
      (node (ref "IC36") (pin "C7") (pinfunction "SGND_1_C7") (pintype "passive"))
      (node (ref "IC36") (pin "D1") (pinfunction "GND_5_D1") (pintype "passive"))
      (node (ref "IC36") (pin "D10") (pinfunction "GND_10_D10") (pintype "passive"))
      (node (ref "IC36") (pin "D11") (pinfunction "GND_11_D11") (pintype "passive"))
      (node (ref "IC36") (pin "D12") (pinfunction "GND_12_D12") (pintype "passive"))
      (node (ref "IC36") (pin "D2") (pinfunction "GND_6_D2") (pintype "passive"))
      (node (ref "IC36") (pin "D3") (pinfunction "GND_7_D3") (pintype "passive"))
      (node (ref "IC36") (pin "D4") (pinfunction "GND_8_D4") (pintype "passive"))
      (node (ref "IC36") (pin "D6") (pinfunction "SGND_2_D6") (pintype "passive"))
      (node (ref "IC36") (pin "D9") (pinfunction "GND_9_D9") (pintype "passive"))
      (node (ref "IC36") (pin "E1") (pinfunction "GND_13_E1") (pintype "passive"))
      (node (ref "IC36") (pin "E10") (pinfunction "GND_17_E10") (pintype "passive"))
      (node (ref "IC36") (pin "E11") (pinfunction "GND_18_E11") (pintype "passive"))
      (node (ref "IC36") (pin "E12") (pinfunction "GND_19_E12") (pintype "passive"))
      (node (ref "IC36") (pin "E2") (pinfunction "GND_14_E2") (pintype "passive"))
      (node (ref "IC36") (pin "E3") (pinfunction "GND_15_E3") (pintype "passive"))
      (node (ref "IC36") (pin "E4") (pinfunction "GND_16_E4") (pintype "passive"))
      (node (ref "IC36") (pin "F1") (pinfunction "GND_20_F1") (pintype "passive"))
      (node (ref "IC36") (pin "F10") (pinfunction "GND_23_F10") (pintype "passive"))
      (node (ref "IC36") (pin "F11") (pinfunction "GND_24_F11") (pintype "passive"))
      (node (ref "IC36") (pin "F12") (pinfunction "GND_25_F12") (pintype "passive"))
      (node (ref "IC36") (pin "F2") (pinfunction "GND_21_F2") (pintype "passive"))
      (node (ref "IC36") (pin "F3") (pinfunction "GND_22_F3") (pintype "passive"))
      (node (ref "IC36") (pin "F4") (pinfunction "MODE_PLLIN_F4") (pintype "passive"))
      (node (ref "IC36") (pin "F6") (pinfunction "SGND_3_F6") (pintype "passive"))
      (node (ref "IC36") (pin "F7") (pinfunction "SGND_4_F7") (pintype "passive"))
      (node (ref "IC36") (pin "G1") (pinfunction "GND_26_G1") (pintype "passive"))
      (node (ref "IC36") (pin "G10") (pinfunction "GND_28_G10") (pintype "passive"))
      (node (ref "IC36") (pin "G12") (pinfunction "GND_29_G12") (pintype "passive"))
      (node (ref "IC36") (pin "G3") (pinfunction "GND_27_G3") (pintype "passive"))
      (node (ref "IC36") (pin "G4") (pinfunction "PHASMD_G4") (pintype "passive"))
      (node (ref "IC36") (pin "G6") (pinfunction "SGND_5_G6") (pintype "passive"))
      (node (ref "IC36") (pin "G7") (pinfunction "SGND_6_G7") (pintype "passive"))
      (node (ref "IC36") (pin "H1") (pinfunction "GND_30_H1") (pintype "passive"))
      (node (ref "IC36") (pin "H10") (pinfunction "GND_38_H10") (pintype "passive"))
      (node (ref "IC36") (pin "H11") (pinfunction "GND_39_H11") (pintype "passive"))
      (node (ref "IC36") (pin "H12") (pinfunction "GND_40_H12") (pintype "passive"))
      (node (ref "IC36") (pin "H2") (pinfunction "GND_31_H2") (pintype "passive"))
      (node (ref "IC36") (pin "H3") (pinfunction "GND_32_H3") (pintype "passive"))
      (node (ref "IC36") (pin "H4") (pinfunction "GND_33_H4") (pintype "passive"))
      (node (ref "IC36") (pin "H5") (pinfunction "GND_34_H5") (pintype "passive"))
      (node (ref "IC36") (pin "H6") (pinfunction "GND_35_H6") (pintype "passive"))
      (node (ref "IC36") (pin "H7") (pinfunction "GND_36_H7") (pintype "passive"))
      (node (ref "IC36") (pin "H9") (pinfunction "GND_37_H9") (pintype "passive"))
      (node (ref "IC36") (pin "J1") (pinfunction "GND_41_J1") (pintype "passive"))
      (node (ref "IC36") (pin "J12") (pinfunction "GND_44_J12") (pintype "passive"))
      (node (ref "IC36") (pin "J5") (pinfunction "GND_42_J5") (pintype "passive"))
      (node (ref "IC36") (pin "J8") (pinfunction "GND_43_J8") (pintype "passive"))
      (node (ref "IC36") (pin "K1") (pinfunction "GND_45_K1") (pintype "passive"))
      (node (ref "IC36") (pin "K12") (pinfunction "GND_50_K12") (pintype "passive"))
      (node (ref "IC36") (pin "K5") (pinfunction "GND_46_K5") (pintype "passive"))
      (node (ref "IC36") (pin "K6") (pinfunction "GND_47_K6") (pintype "passive"))
      (node (ref "IC36") (pin "K7") (pinfunction "GND_48_K7") (pintype "passive"))
      (node (ref "IC36") (pin "K8") (pinfunction "GND_49_K8") (pintype "passive"))
      (node (ref "IC36") (pin "L1") (pinfunction "GND_51_L1") (pintype "passive"))
      (node (ref "IC36") (pin "L12") (pinfunction "GND_52_L12") (pintype "passive"))
      (node (ref "IC36") (pin "M1") (pinfunction "GND_53_M1") (pintype "passive"))
      (node (ref "IC36") (pin "M12") (pinfunction "GND_54_M12") (pintype "passive"))
      (node (ref "P10") (pin "1") (pinfunction "1_1") (pintype "passive"))
      (node (ref "R278") (pin "1") (pinfunction "1_1") (pintype "passive"))
      (node (ref "R283") (pin "1") (pinfunction "1_1") (pintype "passive"))
      (node (ref "R284") (pin "1") (pinfunction "1_1") (pintype "passive"))
      (node (ref "R286") (pin "1") (pinfunction "1_1") (pintype "passive"))
      (node (ref "R288") (pin "1") (pinfunction "1_1") (pintype "passive"))
      (node (ref "R289") (pin "1") (pinfunction "1_1") (pintype "passive"))
      (node (ref "R290") (pin "1") (pinfunction "1_1") (pintype "passive"))
      (node (ref "R299") (pin "1") (pinfunction "1_1") (pintype "passive"))
      (node (ref "R300") (pin "2") (pinfunction "2_2") (pintype "passive"))
      (node (ref "R303") (pin "2") (pinfunction "2_2") (pintype "passive"))
      (node (ref "R305") (pin "2") (pinfunction "2_2") (pintype "passive"))
      (node (ref "R307") (pin "1") (pinfunction "1_1") (pintype "passive"))
      (node (ref "U6") (pin "3") (pinfunction "GND_3") (pintype "power_in"))
      (node (ref "U7") (pin "3") (pinfunction "GND_3") (pintype "power_in"))
    )
    (net (code "19") (name "Net-(C593-Pad2)") (class "Default")
      (node (ref "C593") (pin "2") (pinfunction "2_2") (pintype "passive"))
      (node (ref "C594") (pin "1") (pinfunction "1_1") (pintype "passive"))
      (node (ref "C595") (pin "2") (pinfunction "2_2") (pintype "passive"))
      (node (ref "L35") (pin "1") (pinfunction "1_1") (pintype "passive"))
      (node (ref "R277") (pin "1") (pinfunction "1_1") (pintype "passive"))
      (node (ref "R283") (pin "2") (pinfunction "2_2") (pintype "passive"))
    )
    (net (code "20") (name "Net-(C600-Pad2)") (class "Default")
      (node (ref "C600") (pin "2") (pinfunction "2_2") (pintype "passive"))
      (node (ref "R280") (pin "1") (pinfunction "1_1") (pintype "passive"))
    )
    (net (code "21") (name "Net-(C612-Pad2)") (class "Default")
      (node (ref "C612") (pin "2") (pinfunction "2_2") (pintype "passive"))
      (node (ref "F1") (pin "2") (pinfunction "2_2") (pintype "passive"))
      (node (ref "L37") (pin "1") (pinfunction "1_1") (pintype "passive"))
    )
    (net (code "22") (name "Net-(C613-Pad1)") (class "Default")
      (node (ref "C613") (pin "1") (pinfunction "1_1") (pintype "passive"))
      (node (ref "L37") (pin "3") (pinfunction "3_3") (pintype "passive"))
      (node (ref "L38") (pin "1") (pinfunction "1_1") (pintype "passive"))
    )
    (net (code "23") (name "Net-(C613-Pad2)") (class "Default")
      (node (ref "C613") (pin "2") (pinfunction "2_2") (pintype "passive"))
      (node (ref "L36") (pin "1") (pinfunction "1_1") (pintype "passive"))
      (node (ref "L37") (pin "2") (pinfunction "2_2") (pintype "passive"))
    )
    (net (code "24") (name "Net-(C643-Pad1)") (class "Default")
      (node (ref "C643") (pin "1") (pinfunction "1_1") (pintype "passive"))
      (node (ref "R304") (pin "1") (pinfunction "1_1") (pintype "passive"))
    )
    (net (code "25") (name "Net-(D4-A)") (class "Default")
      (node (ref "C612") (pin "1") (pinfunction "1_1") (pintype "passive"))
      (node (ref "D4") (pin "2") (pinfunction "A_2") (pintype "passive"))
      (node (ref "J6") (pin "2") (pinfunction "2_2") (pintype "passive"))
      (node (ref "L37") (pin "4") (pinfunction "4_4") (pintype "passive"))
    )
    (net (code "26") (name "Net-(D4-K)") (class "Default")
      (node (ref "D4") (pin "1") (pinfunction "K_1") (pintype "passive"))
      (node (ref "F1") (pin "1") (pinfunction "1_1") (pintype "passive"))
      (node (ref "J6") (pin "1") (pinfunction "1_1") (pintype "passive"))
    )
    (net (code "27") (name "Net-(IC31-ITH)") (class "Default")
      (node (ref "C601") (pin "2") (pinfunction "2_2") (pintype "passive"))
      (node (ref "IC31") (pin "10") (pinfunction "ITH_10") (pintype "passive"))
      (node (ref "R280") (pin "2") (pinfunction "2_2") (pintype "passive"))
    )
    (net (code "28") (name "Net-(IC31-SHDN{slash}RT)") (class "Default")
      (node (ref "IC31") (pin "1") (pinfunction "SHDN/RT_1") (pintype "passive"))
      (node (ref "R278") (pin "2") (pinfunction "2_2") (pintype "passive"))
    )
    (net (code "29") (name "Net-(IC31-SW)") (class "Default")
      (node (ref "IC31") (pin "4") (pinfunction "SW_4") (pintype "passive"))
      (node (ref "L35") (pin "2") (pinfunction "2_2") (pintype "passive"))
    )
    (net (code "30") (name "Net-(IC32-ADJ)") (class "Default")
      (node (ref "IC32") (pin "8") (pinfunction "ADJ_8") (pintype "passive"))
      (node (ref "R279") (pin "1") (pinfunction "1_1") (pintype "passive"))
      (node (ref "R286") (pin "2") (pinfunction "2_2") (pintype "passive"))
    )
    (net (code "31") (name "Net-(IC32-IMAX)") (class "Default")
      (node (ref "C604") (pin "1") (pinfunction "1_1") (pintype "passive"))
      (node (ref "IC32") (pin "5") (pinfunction "IMAX_5") (pintype "passive"))
      (node (ref "R289") (pin "2") (pinfunction "2_2") (pintype "passive"))
    )
    (net (code "32") (name "Net-(IC32-PWRGD)") (class "Default")
      (node (ref "IC32") (pin "4") (pinfunction "PWRGD_4") (pintype "passive"))
      (node (ref "R285") (pin "1") (pinfunction "1_1") (pintype "passive"))
      (node (ref "U6") (pin "2") (pinfunction "A_2") (pintype "input"))
    )
    (net (code "33") (name "Net-(IC32-REF{slash}BYP)") (class "Default")
      (node (ref "C605") (pin "1") (pinfunction "1_1") (pintype "passive"))
      (node (ref "IC32") (pin "6") (pinfunction "REF/BYP_6") (pintype "passive"))
    )
    (net (code "34") (name "Net-(IC32-~{SHDN})") (class "Default")
      (node (ref "IC32") (pin "3") (pinfunction "~{SHDN}_3") (pintype "passive"))
      (node (ref "R281") (pin "1") (pinfunction "1_1") (pintype "passive"))
      (node (ref "R284") (pin "2") (pinfunction "2_2") (pintype "passive"))
    )
    (net (code "35") (name "Net-(IC33-ADJ)") (class "Default")
      (node (ref "IC33") (pin "8") (pinfunction "ADJ_8") (pintype "passive"))
      (node (ref "R282") (pin "1") (pinfunction "1_1") (pintype "passive"))
      (node (ref "R288") (pin "2") (pinfunction "2_2") (pintype "passive"))
    )
    (net (code "36") (name "Net-(IC33-IMAX)") (class "Default")
      (node (ref "C608") (pin "1") (pinfunction "1_1") (pintype "passive"))
      (node (ref "IC33") (pin "5") (pinfunction "IMAX_5") (pintype "passive"))
      (node (ref "R290") (pin "2") (pinfunction "2_2") (pintype "passive"))
    )
    (net (code "37") (name "Net-(IC33-PWRGD)") (class "Default")
      (node (ref "IC33") (pin "4") (pinfunction "PWRGD_4") (pintype "passive"))
      (node (ref "R287") (pin "1") (pinfunction "1_1") (pintype "passive"))
      (node (ref "U7") (pin "2") (pinfunction "A_2") (pintype "input"))
    )
    (net (code "38") (name "Net-(IC33-REF{slash}BYP)") (class "Default")
      (node (ref "C609") (pin "1") (pinfunction "1_1") (pintype "passive"))
      (node (ref "IC33") (pin "6") (pinfunction "REF/BYP_6") (pintype "passive"))
    )
    (net (code "39") (name "Net-(IC35A-INTVCC)") (class "Default")
      (node (ref "C640") (pin "1") (pinfunction "1_1") (pintype "passive"))
      (node (ref "IC35") (pin "H8") (pinfunction "INTVCC_H8") (pintype "passive"))
      (node (ref "R298") (pin "2") (pinfunction "2_2") (pintype "passive"))
    )
    (net (code "40") (name "Net-(IC35A-PGOOD1)") (class "Default")
      (node (ref "IC35") (pin "G8") (pinfunction "PGOOD2_G8") (pintype "passive"))
      (node (ref "IC35") (pin "G9") (pinfunction "PGOOD1_G9") (pintype "passive"))
      (node (ref "R298") (pin "1") (pinfunction "1_1") (pintype "passive"))
    )
    (net (code "41") (name "Net-(IC35A-TEMP)") (class "Default")
      (node (ref "IC35") (pin "J6") (pinfunction "TEMP_J6") (pintype "passive"))
      (node (ref "R306") (pin "2") (pinfunction "2_2") (pintype "passive"))
    )
    (net (code "42") (name "Net-(IC35A-TRACK1)") (class "Default")
      (node (ref "C638") (pin "2") (pinfunction "2_2") (pintype "passive"))
      (node (ref "IC35") (pin "D8") (pinfunction "TRACK2_D8") (pintype "passive"))
      (node (ref "IC35") (pin "E5") (pinfunction "TRACK1_E5") (pintype "passive"))
    )
    (net (code "43") (name "Net-(IC35B-DIFFOUT)") (class "Default")
      (node (ref "C639") (pin "1") (pinfunction "1_1") (pintype "passive"))
      (node (ref "IC35") (pin "C5") (pinfunction "VOUTS1_C5") (pintype "passive"))
      (node (ref "IC35") (pin "F8") (pinfunction "DIFFOUT_F8") (pintype "passive"))
    )
    (net (code "44") (name "Net-(IC35B-VFB1)") (class "Default")
      (node (ref "C639") (pin "2") (pinfunction "2_2") (pintype "passive"))
      (node (ref "IC35") (pin "D5") (pinfunction "VFB1_D5") (pintype "passive"))
      (node (ref "IC35") (pin "D7") (pinfunction "VFB2_D7") (pintype "passive"))
      (node (ref "R299") (pin "2") (pinfunction "2_2") (pintype "passive"))
    )
    (net (code "45") (name "Net-(IC35C-FSET)") (class "Default")
      (node (ref "IC35") (pin "C6") (pinfunction "FSET_C6") (pintype "passive"))
      (node (ref "R307") (pin "2") (pinfunction "2_2") (pintype "passive"))
    )
    (net (code "46") (name "Net-(IC36A-INTVCC)") (class "Default")
      (node (ref "C642") (pin "1") (pinfunction "1_1") (pintype "passive"))
      (node (ref "IC36") (pin "C6") (pinfunction "FSET_C6") (pintype "passive"))
      (node (ref "IC36") (pin "H8") (pinfunction "INTVCC_H8") (pintype "passive"))
      (node (ref "R302") (pin "2") (pinfunction "2_2") (pintype "passive"))
    )
    (net (code "47") (name "Net-(IC36A-PGOOD1)") (class "Default")
      (node (ref "IC36") (pin "G8") (pinfunction "PGOOD2_G8") (pintype "passive"))
      (node (ref "IC36") (pin "G9") (pinfunction "PGOOD1_G9") (pintype "passive"))
      (node (ref "R302") (pin "1") (pinfunction "1_1") (pintype "passive"))
    )
    (net (code "48") (name "Net-(IC36A-TRACK1)") (class "Default")
      (node (ref "C641") (pin "2") (pinfunction "2_2") (pintype "passive"))
      (node (ref "IC36") (pin "D8") (pinfunction "TRACK2_D8") (pintype "passive"))
      (node (ref "IC36") (pin "E5") (pinfunction "TRACK1_E5") (pintype "passive"))
    )
    (net (code "49") (name "Net-(IC36B-VFB1)") (class "Default")
      (node (ref "IC36") (pin "D5") (pinfunction "VFB1_D5") (pintype "passive"))
      (node (ref "R303") (pin "1") (pinfunction "1_1") (pintype "passive"))
    )
    (net (code "50") (name "Net-(IC36B-VFB2)") (class "Default")
      (node (ref "IC36") (pin "D7") (pinfunction "VFB2_D7") (pintype "passive"))
      (node (ref "R305") (pin "1") (pinfunction "1_1") (pintype "passive"))
    )
    (net (code "51") (name "Net-(Q2-G)") (class "Default")
      (node (ref "C618") (pin "1") (pinfunction "1_1") (pintype "passive"))
      (node (ref "Q2") (pin "4") (pinfunction "G_4") (pintype "passive"))
      (node (ref "R293") (pin "1") (pinfunction "1_1") (pintype "passive"))
      (node (ref "R294") (pin "2") (pinfunction "2_2") (pintype "passive"))
    )
    (net (code "52") (name "Net-(Q2-S_1)") (class "Default")
      (node (ref "C618") (pin "2") (pinfunction "2_2") (pintype "passive"))
      (node (ref "L36") (pin "2") (pinfunction "2_2") (pintype "passive"))
      (node (ref "Q2") (pin "1") (pinfunction "S_1_1") (pintype "passive"))
      (node (ref "Q2") (pin "2") (pinfunction "S_2_2") (pintype "passive"))
      (node (ref "Q2") (pin "3") (pinfunction "S_3_3") (pintype "passive"))
      (node (ref "R293") (pin "2") (pinfunction "2_2") (pintype "passive"))
    )
    (net (code "53") (name "Net-(R275-Pad1)") (class "Default")
      (node (ref "R275") (pin "1") (pinfunction "1_1") (pintype "passive"))
      (node (ref "R279") (pin "2") (pinfunction "2_2") (pintype "passive"))
    )
    (net (code "54") (name "Net-(R276-Pad1)") (class "Default")
      (node (ref "R276") (pin "1") (pinfunction "1_1") (pintype "passive"))
      (node (ref "R282") (pin "2") (pinfunction "2_2") (pintype "passive"))
    )
    (net (code "55") (name "Net-(U6A-Y)") (class "Default")
      (node (ref "R291") (pin "2") (pinfunction "2_2") (pintype "passive"))
      (node (ref "U6") (pin "4") (pinfunction "Y_4") (pintype "open_collector"))
    )
    (net (code "56") (name "Net-(U7A-Y)") (class "Default")
      (node (ref "R292") (pin "2") (pinfunction "2_2") (pintype "passive"))
      (node (ref "U7") (pin "4") (pinfunction "Y_4") (pintype "open_collector"))
    )
    (net (code "57") (name "S1VDD_SRC") (class "Default")
      (node (ref "C597") (pin "1") (pinfunction "1_1") (pintype "passive"))
      (node (ref "IC33") (pin "10") (pinfunction "OUT_2_10") (pintype "passive"))
      (node (ref "IC33") (pin "9") (pinfunction "OUT_1_9") (pintype "passive"))
      (node (ref "R276") (pin "2") (pinfunction "2_2") (pintype "passive"))
    )
    (net (code "58") (name "unconnected-(IC31-PGOOD-Pad8)") (class "Default")
      (node (ref "IC31") (pin "8") (pinfunction "PGOOD_8") (pintype "passive+no_connect"))
    )
    (net (code "59") (name "unconnected-(IC34-NC-Pad3)") (class "Default")
      (node (ref "IC34") (pin "3") (pinfunction "NC_3") (pintype "passive+no_connect"))
    )
    (net (code "60") (name "unconnected-(IC34-VBUS-Pad8)") (class "Default")
      (node (ref "IC34") (pin "8") (pinfunction "VBUS_8") (pintype "passive"))
    )
    (net (code "61") (name "unconnected-(IC35A-CLKOUT-PadG5)") (class "Default")
      (node (ref "IC35") (pin "G5") (pinfunction "CLKOUT_G5") (pintype "passive+no_connect"))
    )
    (net (code "62") (name "unconnected-(IC35A-EXTVCC-PadJ7)") (class "Default")
      (node (ref "IC35") (pin "J7") (pinfunction "EXTVCC_J7") (pintype "passive+no_connect"))
    )
    (net (code "63") (name "unconnected-(IC35A-SW1-PadG2)") (class "Default")
      (node (ref "IC35") (pin "G2") (pinfunction "SW1_G2") (pintype "passive+no_connect"))
    )
    (net (code "64") (name "unconnected-(IC35A-SW2-PadG11)") (class "Default")
      (node (ref "IC35") (pin "G11") (pinfunction "SW2_G11") (pintype "passive+no_connect"))
    )
    (net (code "65") (name "unconnected-(IC36A-CLKOUT-PadG5)") (class "Default")
      (node (ref "IC36") (pin "G5") (pinfunction "CLKOUT_G5") (pintype "passive+no_connect"))
    )
    (net (code "66") (name "unconnected-(IC36A-EXTVCC-PadJ7)") (class "Default")
      (node (ref "IC36") (pin "J7") (pinfunction "EXTVCC_J7") (pintype "passive+no_connect"))
    )
    (net (code "67") (name "unconnected-(IC36A-SW1-PadG2)") (class "Default")
      (node (ref "IC36") (pin "G2") (pinfunction "SW1_G2") (pintype "passive+no_connect"))
    )
    (net (code "68") (name "unconnected-(IC36A-SW2-PadG11)") (class "Default")
      (node (ref "IC36") (pin "G11") (pinfunction "SW2_G11") (pintype "passive+no_connect"))
    )
    (net (code "69") (name "unconnected-(IC36A-TEMP-PadJ6)") (class "Default")
      (node (ref "IC36") (pin "J6") (pinfunction "TEMP_J6") (pintype "passive+no_connect"))
    )
    (net (code "70") (name "unconnected-(U6B-NC-Pad1)") (class "Default")
      (node (ref "U6") (pin "1") (pinfunction "NC_1") (pintype "passive+no_connect"))
    )
    (net (code "71") (name "unconnected-(U7B-NC-Pad1)") (class "Default")
      (node (ref "U7") (pin "1") (pinfunction "NC_1") (pintype "passive+no_connect"))
    )
  )
)
